# LrAc.net
KiCad netlist of a schematic drawn in Altium Designer
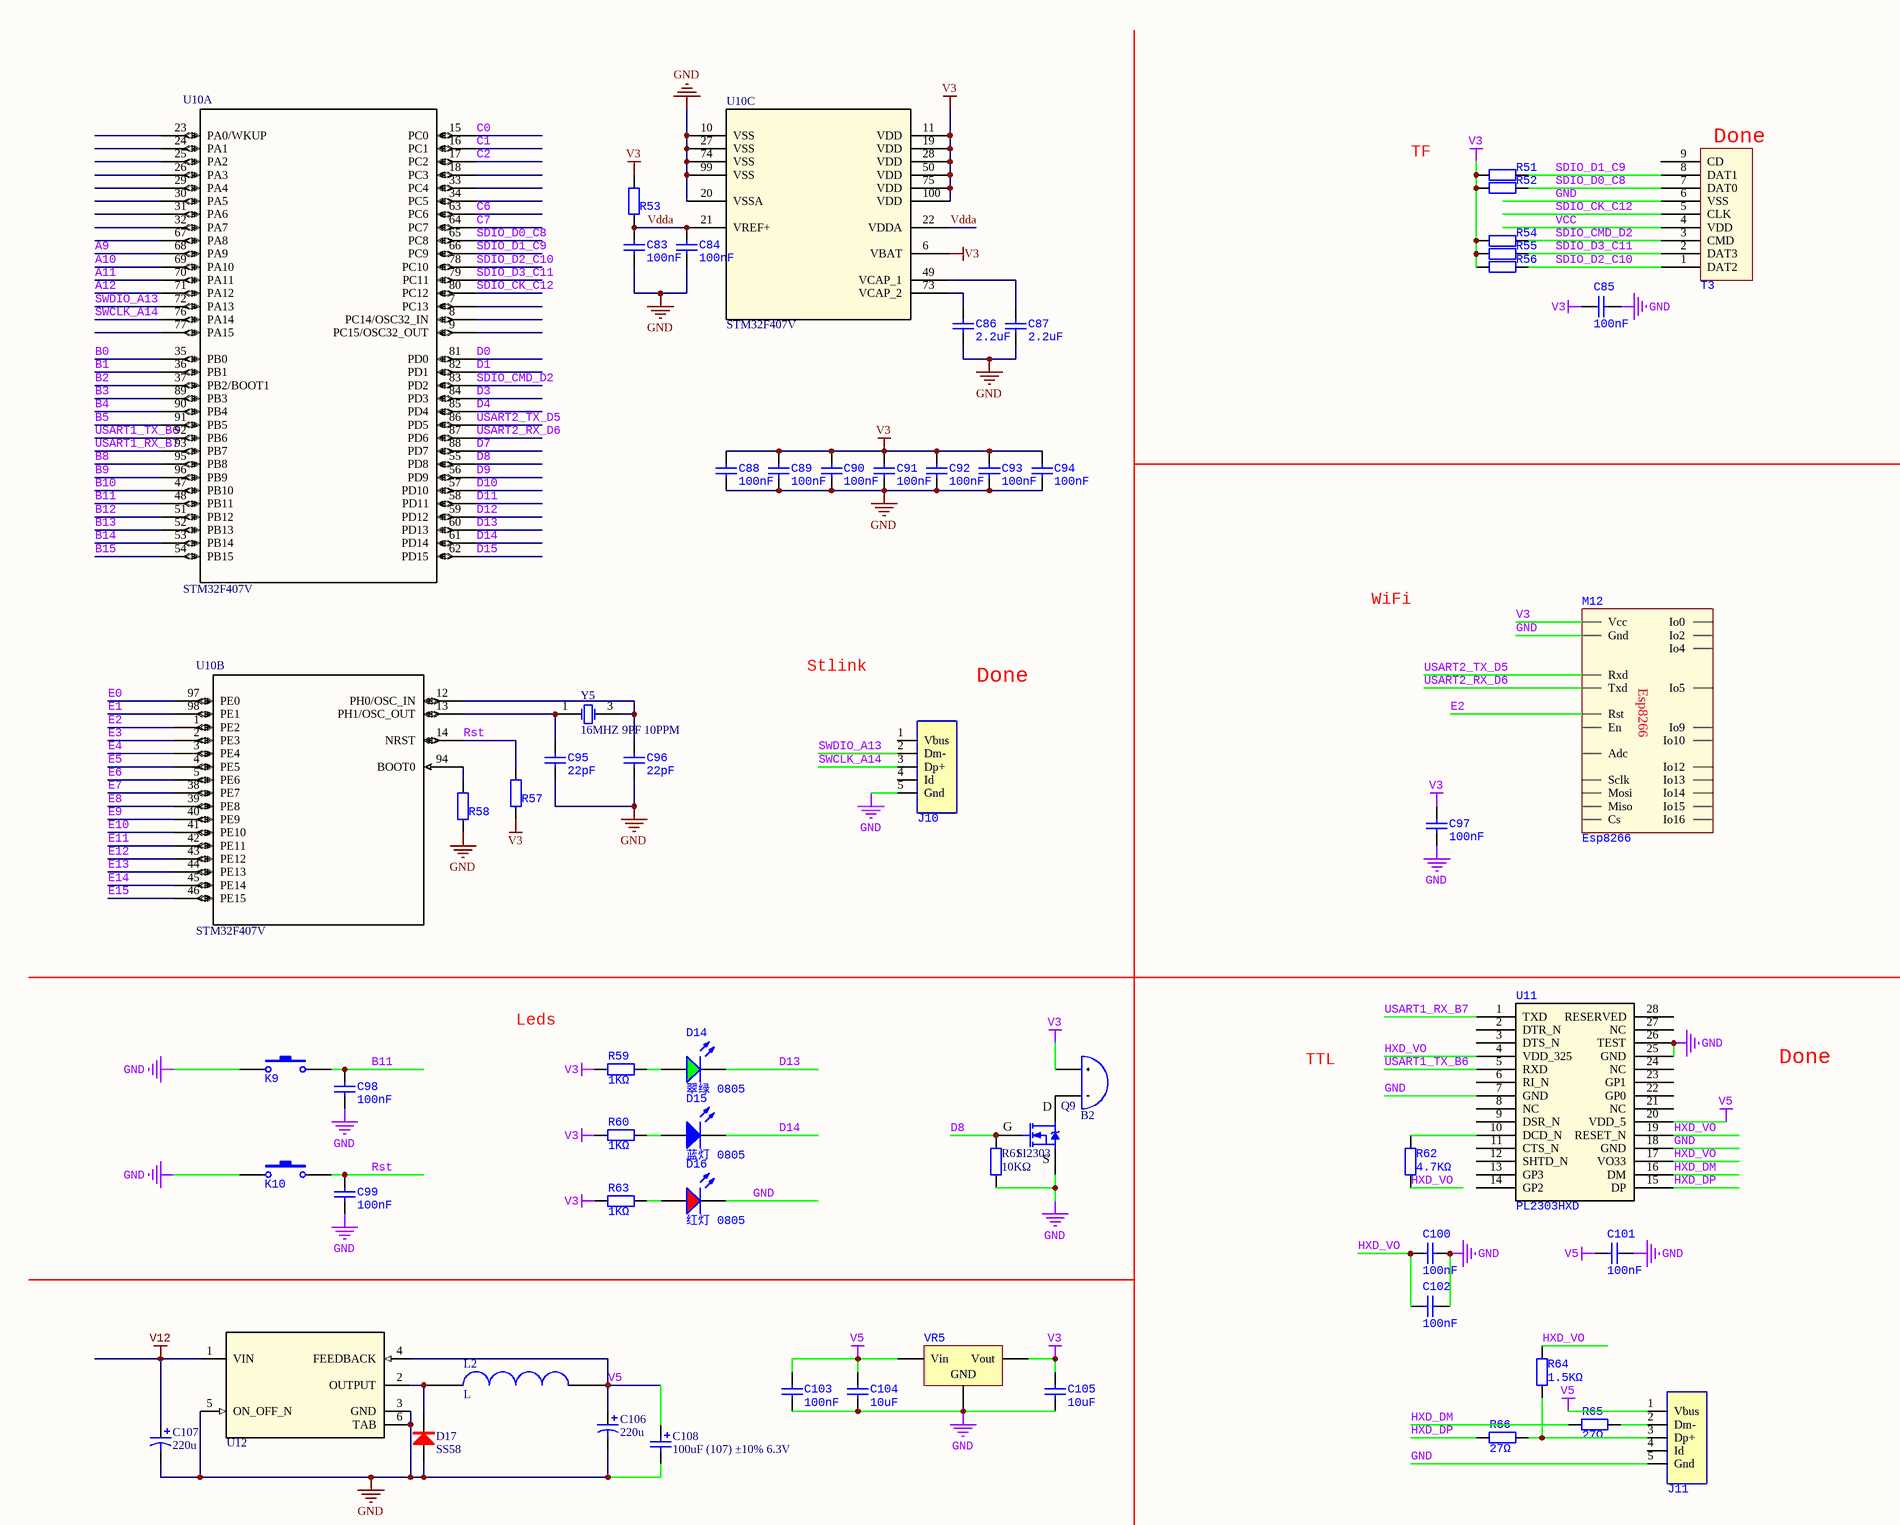
[diagram p0: LrAc.SchDoc, top]
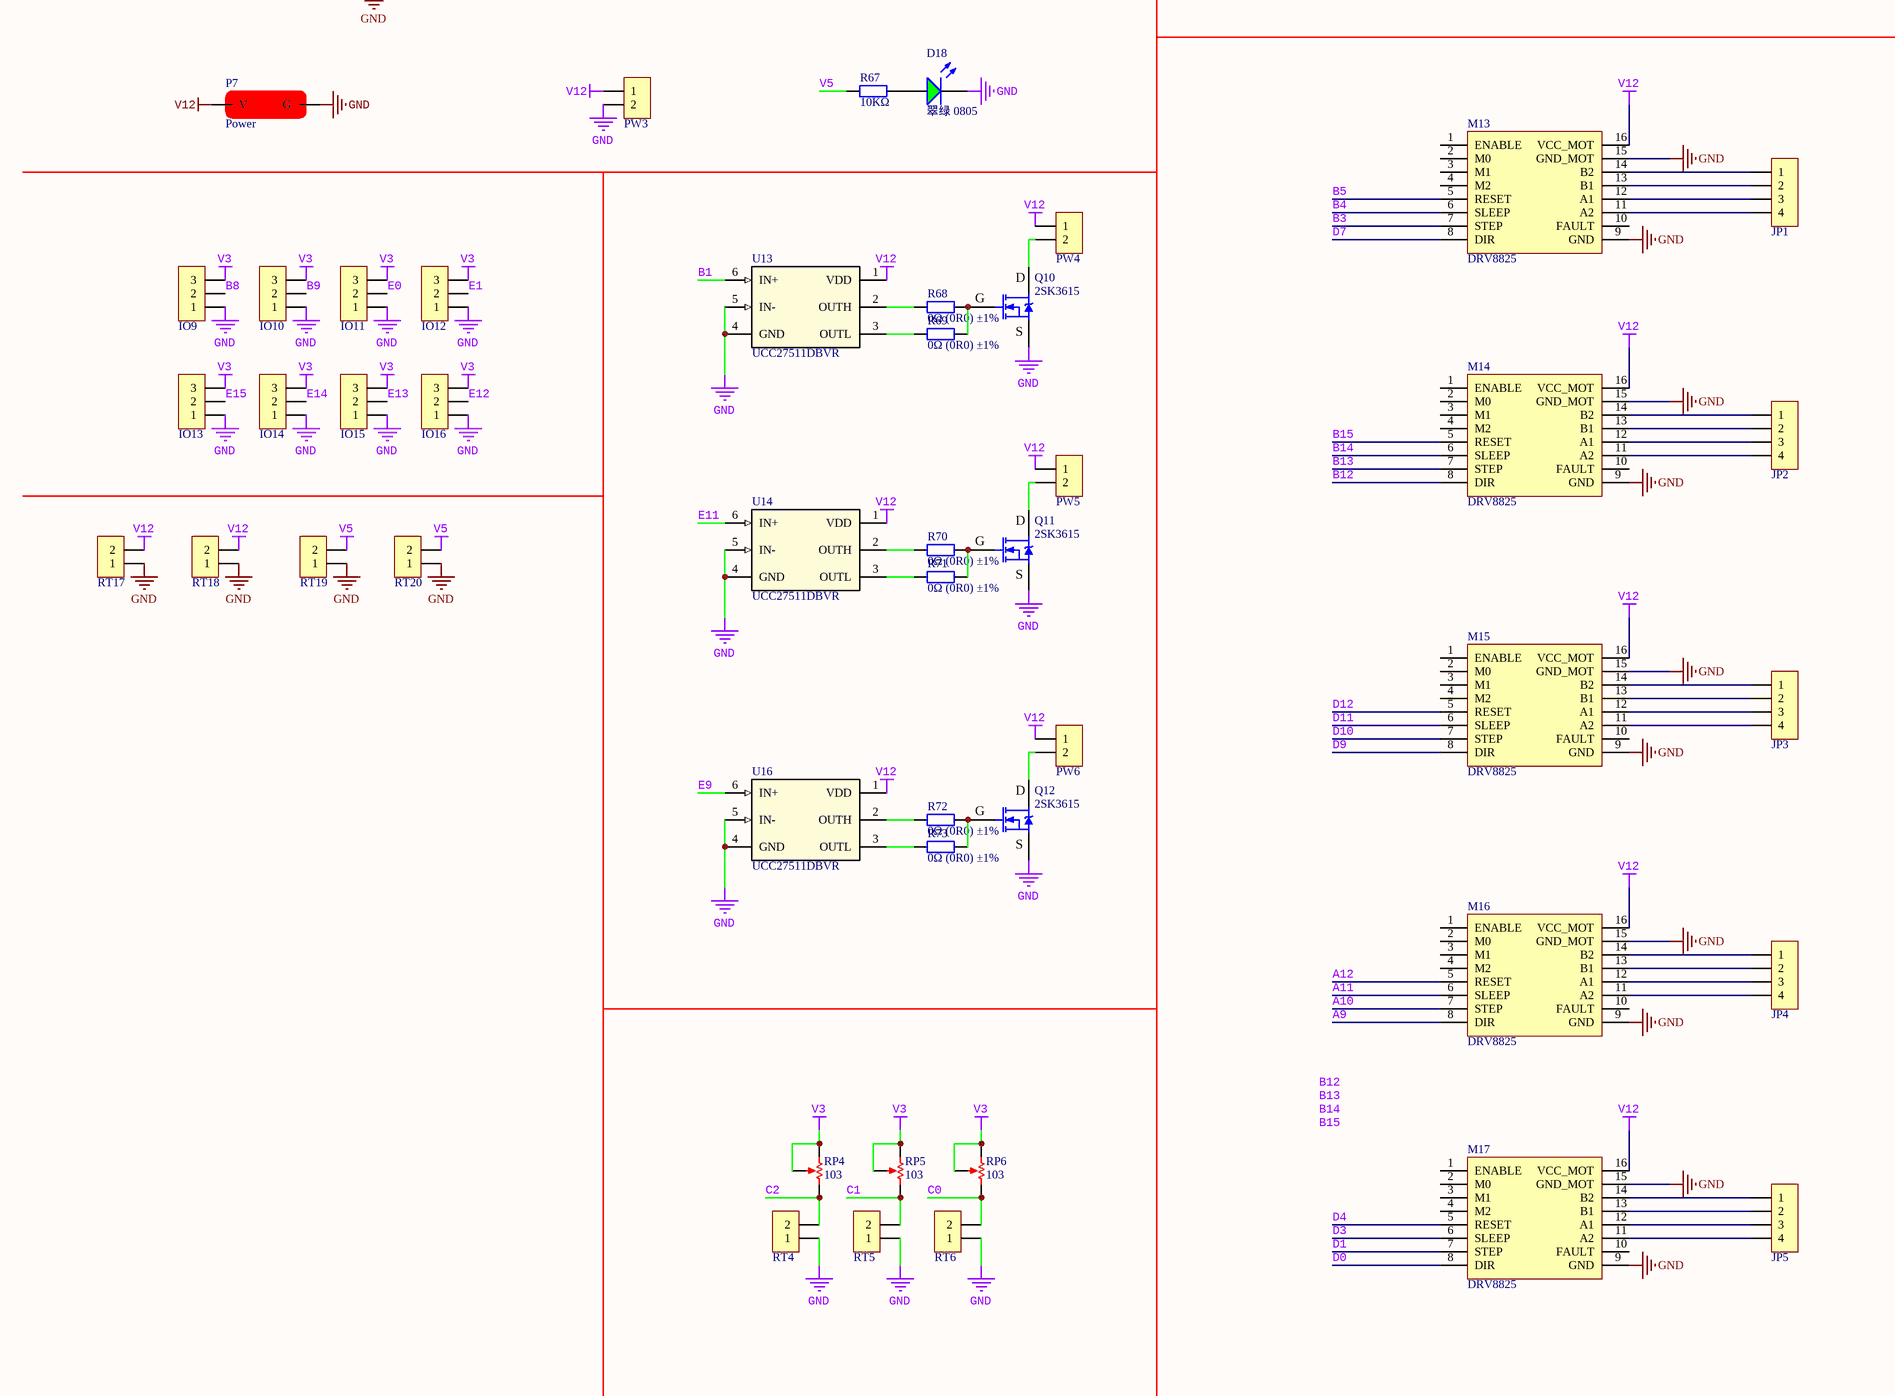
[diagram p1: LrAc.SchDoc, bottom]

(export (version "E")
  (design (tool "Eeschema 10.0.6"))
  (components
    (comp (ref "B2")
      (value "Bell")
      (footprint "BELL11.9")
      (description "蜂鸣器")
      (libsource (lib "BasicLib") (part "Bell"))
    )
    (comp (ref "C83")
      (value "100nF")
      (footprint "0603_C")
      (description "贴片电容")
      (libsource (lib "Miscellaneous Devices LC") (part "0603 100nF (104) 10% 50V"))
    )
    (comp (ref "C84")
      (value "100nF")
      (footprint "0603_C")
      (description "贴片电容")
      (libsource (lib "Miscellaneous Devices LC") (part "0603 100nF (104) 10% 50V"))
    )
    (comp (ref "C85")
      (value "100nF")
      (footprint "0603_C")
      (description "贴片电容")
      (libsource (lib "Miscellaneous Devices LC") (part "0603 100nF (104) 10% 50V"))
    )
    (comp (ref "C86")
      (value "2.2uF")
      (footprint "0603_C")
      (description "贴片电容")
      (libsource (lib "Miscellaneous Devices LC") (part "0603 100nF (104) 10% 50V"))
    )
    (comp (ref "C87")
      (value "2.2uF")
      (footprint "0603_C")
      (description "贴片电容")
      (libsource (lib "Miscellaneous Devices LC") (part "0603 100nF (104) 10% 50V"))
    )
    (comp (ref "C88")
      (value "100nF")
      (footprint "0603_C")
      (description "贴片电容")
      (libsource (lib "Miscellaneous Devices LC") (part "0603 100nF (104) 10% 50V"))
    )
    (comp (ref "C89")
      (value "100nF")
      (footprint "0603_C")
      (description "贴片电容")
      (libsource (lib "Miscellaneous Devices LC") (part "0603 100nF (104) 10% 50V"))
    )
    (comp (ref "C90")
      (value "100nF")
      (footprint "0603_C")
      (description "贴片电容")
      (libsource (lib "Miscellaneous Devices LC") (part "0603 100nF (104) 10% 50V"))
    )
    (comp (ref "C91")
      (value "100nF")
      (footprint "0603_C")
      (description "贴片电容")
      (libsource (lib "Miscellaneous Devices LC") (part "0603 100nF (104) 10% 50V"))
    )
    (comp (ref "C92")
      (value "100nF")
      (footprint "0603_C")
      (description "贴片电容")
      (libsource (lib "Miscellaneous Devices LC") (part "0603 100nF (104) 10% 50V"))
    )
    (comp (ref "C93")
      (value "100nF")
      (footprint "0603_C")
      (description "贴片电容")
      (libsource (lib "Miscellaneous Devices LC") (part "0603 100nF (104) 10% 50V"))
    )
    (comp (ref "C94")
      (value "100nF")
      (footprint "0603_C")
      (description "贴片电容")
      (libsource (lib "Miscellaneous Devices LC") (part "0603 100nF (104) 10% 50V"))
    )
    (comp (ref "C95")
      (value "22pF")
      (footprint "0603_C")
      (description "贴片电容")
      (libsource (lib "Miscellaneous Devices LC") (part "0603 100nF (104) 10% 50V"))
    )
    (comp (ref "C96")
      (value "22pF")
      (footprint "0603_C")
      (description "贴片电容")
      (libsource (lib "Miscellaneous Devices LC") (part "0603 100nF (104) 10% 50V"))
    )
    (comp (ref "C97")
      (value "100nF")
      (footprint "0603_C")
      (description "贴片电容")
      (libsource (lib "Miscellaneous Devices LC") (part "0603 100nF (104) 10% 50V"))
    )
    (comp (ref "C98")
      (value "100nF")
      (footprint "0603_C")
      (description "贴片电容")
      (libsource (lib "Miscellaneous Devices LC") (part "0603 100nF (104) 10% 50V"))
    )
    (comp (ref "C99")
      (value "100nF")
      (footprint "0603_C")
      (description "贴片电容")
      (libsource (lib "Miscellaneous Devices LC") (part "0603 100nF (104) 10% 50V"))
    )
    (comp (ref "C100")
      (value "100nF")
      (footprint "0603_C")
      (description "贴片电容")
      (libsource (lib "Miscellaneous Devices LC") (part "0603 100nF (104) 10% 50V"))
    )
    (comp (ref "C101")
      (value "100nF")
      (footprint "0603_C")
      (description "贴片电容")
      (libsource (lib "Miscellaneous Devices LC") (part "0603 100nF (104) 10% 50V"))
    )
    (comp (ref "C102")
      (value "100nF")
      (footprint "0603_C")
      (description "贴片电容")
      (libsource (lib "Miscellaneous Devices LC") (part "0603 100nF (104) 10% 50V"))
    )
    (comp (ref "C103")
      (value "100nF")
      (footprint "0603_C")
      (description "贴片电容")
      (libsource (lib "Miscellaneous Devices LC") (part "0603 100nF (104) 10% 50V"))
    )
    (comp (ref "C104")
      (value "10uF")
      (footprint "0805_C")
      (description "贴片电容")
      (libsource (lib "Miscellaneous Devices LC") (part "0805 10uF (106) 10% 25V"))
    )
    (comp (ref "C105")
      (value "10uF")
      (footprint "0805_C")
      (description "贴片电容")
      (libsource (lib "Miscellaneous Devices LC") (part "0805 10uF (106) 10% 25V"))
    )
    (comp (ref "C106")
      (value "220u")
      (footprint "CM F(10*10.2)")
      (description "Polarized Capacitor (Axial)")
      (fields (field (name "PUBLISHER") "Altium Limited"))
      (libsource (lib "BasicLib") (part "Cp"))
    )
    (comp (ref "C107")
      (value "220u")
      (footprint "CM F(10*10.2)")
      (description "Polarized Capacitor (Axial)")
      (fields (field (name "PUBLISHER") "Altium Limited"))
      (libsource (lib "BasicLib") (part "Cp"))
    )
    (comp (ref "C108")
      (value "100uF (107) ±10% 6.3V")
      (footprint "CASE-B_3528")
      (description "钽电容")
      (libsource (lib "Miscellaneous Devices LC") (part "3528 100uF (107) 10% 6.3V"))
    )
    (comp (ref "D14")
      (value "翠绿 0805")
      (footprint "0805_LED_S1")
      (description "发光二极管")
      (libsource (lib "Miscellaneous Devices LC") (part "0805 翠绿"))
    )
    (comp (ref "D15")
      (value "蓝灯 0805")
      (footprint "0805_LED_S1")
      (description "发光二极管")
      (libsource (lib "Miscellaneous Devices LC") (part "0805 蓝灯"))
    )
    (comp (ref "D16")
      (value "红灯 0805")
      (footprint "0805_LED_S1")
      (description "发光二极管")
      (libsource (lib "Miscellaneous Devices LC") (part "0805 红灯"))
    )
    (comp (ref "D17")
      (value "SS58")
      (footprint "SMA")
      (description "整流二极管")
      (fields (field (name "版权归属") "源创客"))
      (libsource (lib "BasicLib") (part "Dz"))
    )
    (comp (ref "D18")
      (value "翠绿 0805")
      (footprint "0805_LED_S1")
      (description "发光二极管")
      (libsource (lib "Miscellaneous Devices LC") (part "0805 翠绿"))
    )
    (comp (ref "IO9")
      (value "HDR-1X3")
      (footprint "XH2.54-LI-3P")
      (description "3P接插件")
      (fields (field (name "版权归属") "源创客"))
      (libsource (lib "FaceLib") (part "Header 3"))
    )
    (comp (ref "IO10")
      (value "HDR-1X3")
      (footprint "XH2.54-LI-3P")
      (description "3P接插件")
      (fields (field (name "版权归属") "源创客"))
      (libsource (lib "FaceLib") (part "Header 3"))
    )
    (comp (ref "IO11")
      (value "HDR-1X3")
      (footprint "XH2.54-LI-3P")
      (description "3P接插件")
      (fields (field (name "版权归属") "源创客"))
      (libsource (lib "FaceLib") (part "Header 3"))
    )
    (comp (ref "IO12")
      (value "HDR-1X3")
      (footprint "XH2.54-LI-3P")
      (description "3P接插件")
      (fields (field (name "版权归属") "源创客"))
      (libsource (lib "FaceLib") (part "Header 3"))
    )
    (comp (ref "IO13")
      (value "HDR-1X3")
      (footprint "XH2.54-LI-3P")
      (description "3P接插件")
      (fields (field (name "版权归属") "源创客"))
      (libsource (lib "FaceLib") (part "Header 3"))
    )
    (comp (ref "IO14")
      (value "HDR-1X3")
      (footprint "XH2.54-LI-3P")
      (description "3P接插件")
      (fields (field (name "版权归属") "源创客"))
      (libsource (lib "FaceLib") (part "Header 3"))
    )
    (comp (ref "IO15")
      (value "HDR-1X3")
      (footprint "XH2.54-LI-3P")
      (description "3P接插件")
      (fields (field (name "版权归属") "源创客"))
      (libsource (lib "FaceLib") (part "Header 3"))
    )
    (comp (ref "IO16")
      (value "HDR-1X3")
      (footprint "XH2.54-LI-3P")
      (description "3P接插件")
      (fields (field (name "版权归属") "源创客"))
      (libsource (lib "FaceLib") (part "Header 3"))
    )
    (comp (ref "J10") (value "UsbOtg") (footprint "USB-MINI-A") (libsource (lib "BasicLib") (part "UsbOtg")))
    (comp (ref "J11") (value "UsbOtg") (footprint "USB-MICRO_E") (libsource (lib "BasicLib") (part "UsbOtg")))
    (comp (ref "JP1")
      (value "HDR-1X4")
      (footprint "XH2.54-LI-4P")
      (description "4P接插件")
      (fields (field (name "版权归属") "源创客"))
      (libsource (lib "FaceLib") (part "Header 4"))
    )
    (comp (ref "JP2")
      (value "HDR-1X4")
      (footprint "XH2.54-LI-4P")
      (description "4P接插件")
      (fields (field (name "版权归属") "源创客"))
      (libsource (lib "FaceLib") (part "Header 4"))
    )
    (comp (ref "JP3")
      (value "HDR-1X4")
      (footprint "XH2.54-LI-4P")
      (description "4P接插件")
      (fields (field (name "版权归属") "源创客"))
      (libsource (lib "FaceLib") (part "Header 4"))
    )
    (comp (ref "JP4")
      (value "HDR-1X4")
      (footprint "XH2.54-LI-4P")
      (description "4P接插件")
      (fields (field (name "版权归属") "源创客"))
      (libsource (lib "FaceLib") (part "Header 4"))
    )
    (comp (ref "JP5")
      (value "HDR-1X4")
      (footprint "XH2.54-LI-4P")
      (description "4P接插件")
      (fields (field (name "版权归属") "源创客"))
      (libsource (lib "FaceLib") (part "Header 4"))
    )
    (comp (ref "K9")
      (value "SW")
      (footprint "SWITCH")
      (description "Switch")
      (libsource (lib "BasicLib") (part "SW"))
    )
    (comp (ref "K10")
      (value "SW")
      (footprint "SWITCH")
      (description "Switch")
      (libsource (lib "BasicLib") (part "SW"))
    )
    (comp (ref "L2") (value "L") (footprint "CDRH127") (libsource (lib "BasicLib") (part "L")))
    (comp (ref "M12") (value "Esp8266") (footprint "ESP8266") (libsource (lib "ModeLib") (part "Esp8266")))
    (comp (ref "M13")
      (value "DRV8825")
      (footprint "DRV8825")
      (description "步进电机驱动模块")
      (fields (field (name "版权归属") "源创客"))
      (libsource (lib "ModeLib") (part "DRV8825"))
    )
    (comp (ref "M14")
      (value "DRV8825")
      (footprint "DRV8825")
      (description "步进电机驱动模块")
      (fields (field (name "版权归属") "源创客"))
      (libsource (lib "ModeLib") (part "DRV8825"))
    )
    (comp (ref "M15")
      (value "DRV8825")
      (footprint "DRV8825")
      (description "步进电机驱动模块")
      (fields (field (name "版权归属") "源创客"))
      (libsource (lib "ModeLib") (part "DRV8825"))
    )
    (comp (ref "M16")
      (value "DRV8825")
      (footprint "DRV8825")
      (description "步进电机驱动模块")
      (fields (field (name "版权归属") "源创客"))
      (libsource (lib "ModeLib") (part "DRV8825"))
    )
    (comp (ref "M17")
      (value "DRV8825")
      (footprint "DRV8825")
      (description "步进电机驱动模块")
      (fields (field (name "版权归属") "源创客"))
      (libsource (lib "ModeLib") (part "DRV8825"))
    )
    (comp (ref "P7") (value "Power") (footprint "DC-005") (libsource (lib "BasicLib") (part "Power")))
    (comp (ref "PW3")
      (value "HDR-1X2")
      (footprint "2PIN-5.08A")
      (description "2P接插件")
      (fields (field (name "版权归属") "源创客"))
      (libsource (lib "FaceLib") (part "Header 2"))
    )
    (comp (ref "PW4")
      (value "HDR-1X2")
      (footprint "2PIN-5.08A")
      (description "2P接插件")
      (fields (field (name "版权归属") "源创客"))
      (libsource (lib "FaceLib") (part "Header 2"))
    )
    (comp (ref "PW5")
      (value "HDR-1X2")
      (footprint "2PIN-5.08A")
      (description "2P接插件")
      (fields (field (name "版权归属") "源创客"))
      (libsource (lib "FaceLib") (part "Header 2"))
    )
    (comp (ref "PW6")
      (value "HDR-1X2")
      (footprint "2PIN-5.08A")
      (description "2P接插件")
      (fields (field (name "版权归属") "源创客"))
      (libsource (lib "FaceLib") (part "Header 2"))
    )
    (comp (ref "Q9")
      (value "SI2303")
      (footprint "SI2302")
      (description "N沟场效应管")
      (fields (field (name "版权归属") "源创客"))
      (libsource (lib "BasicLib") (part "NMOS"))
    )
    (comp (ref "Q10")
      (value "2SK3615")
      (footprint "IRF3205")
      (description "N沟场效应管")
      (fields (field (name "版权归属") "源创客"))
      (libsource (lib "BasicLib") (part "NMOS"))
    )
    (comp (ref "Q11")
      (value "2SK3615")
      (footprint "IRF3205")
      (description "N沟场效应管")
      (fields (field (name "版权归属") "源创客"))
      (libsource (lib "BasicLib") (part "NMOS"))
    )
    (comp (ref "Q12")
      (value "2SK3615")
      (footprint "IRF3205")
      (description "N沟场效应管")
      (fields (field (name "版权归属") "源创客"))
      (libsource (lib "BasicLib") (part "NMOS"))
    )
    (comp (ref "R51")
      (value "47KΩ")
      (footprint "0603_R")
      (description "贴片电阻")
      (libsource (lib "") (part "0603 47KΩ (4702) 1%_1"))
    )
    (comp (ref "R52")
      (value "47KΩ")
      (footprint "0603_R")
      (description "贴片电阻")
      (libsource (lib "") (part "0603 47KΩ (4702) 1%_1"))
    )
    (comp (ref "R53")
      (value "10Ω")
      (footprint "0603_R")
      (description "贴片电阻")
      (libsource (lib "Miscellaneous Devices LC") (part "0603 47KΩ (4702) 1%"))
    )
    (comp (ref "R54")
      (value "47KΩ")
      (footprint "0603_R")
      (description "贴片电阻")
      (libsource (lib "") (part "0603 47KΩ (4702) 1%_1"))
    )
    (comp (ref "R55")
      (value "47KΩ")
      (footprint "0603_R")
      (description "贴片电阻")
      (libsource (lib "") (part "0603 47KΩ (4702) 1%_1"))
    )
    (comp (ref "R56")
      (value "47KΩ")
      (footprint "0603_R")
      (description "贴片电阻")
      (libsource (lib "") (part "0603 47KΩ (4702) 1%_1"))
    )
    (comp (ref "R57")
      (value "47KΩ")
      (footprint "0603_R")
      (description "贴片电阻")
      (libsource (lib "Miscellaneous Devices LC") (part "0603 47KΩ (4702) 1%"))
    )
    (comp (ref "R58")
      (value "47KΩ")
      (footprint "0603_R")
      (description "贴片电阻")
      (libsource (lib "Miscellaneous Devices LC") (part "0603 47KΩ (4702) 1%"))
    )
    (comp (ref "R59")
      (value "1KΩ")
      (footprint "0603_R")
      (description "贴片电阻")
      (libsource (lib "Miscellaneous Devices LC") (part "0603 10KΩ (1002) 1%"))
    )
    (comp (ref "R60")
      (value "1KΩ")
      (footprint "0603_R")
      (description "贴片电阻")
      (libsource (lib "Miscellaneous Devices LC") (part "0603 10KΩ (1002) 1%"))
    )
    (comp (ref "R61")
      (value "10KΩ")
      (footprint "0805_R")
      (description "贴片电阻")
      (libsource (lib "") (part "0805 10KΩ (1002) 1%_1"))
    )
    (comp (ref "R62")
      (value "4.7KΩ")
      (footprint "0603_R")
      (description "贴片电阻")
      (libsource (lib "") (part "0603 10KΩ (1002) 1%_3"))
    )
    (comp (ref "R63")
      (value "1KΩ")
      (footprint "0603_R")
      (description "贴片电阻")
      (libsource (lib "Miscellaneous Devices LC") (part "0603 10KΩ (1002) 1%"))
    )
    (comp (ref "R64")
      (value "1.5KΩ")
      (footprint "0603_R")
      (description "贴片电阻")
      (libsource (lib "") (part "0603 10KΩ (1002) 1%_2"))
    )
    (comp (ref "R65")
      (value "27Ω")
      (footprint "0603_R")
      (description "贴片电阻")
      (libsource (lib "") (part "0603 10KΩ (1002) 1%_1"))
    )
    (comp (ref "R66")
      (value "27Ω")
      (footprint "0603_R")
      (description "贴片电阻")
      (libsource (lib "") (part "0603 10KΩ (1002) 1%_1"))
    )
    (comp (ref "R67")
      (value "10KΩ")
      (footprint "0805_R")
      (description "贴片电阻")
      (libsource (lib "Miscellaneous Devices LC") (part "0805 10KΩ (1002) 1%"))
    )
    (comp (ref "R68")
      (value "0Ω (0R0) ±1%")
      (footprint "0805_R")
      (description "贴片电阻")
      (libsource (lib "Miscellaneous Devices LC") (part "0805 0Ω (0R0) 1%"))
    )
    (comp (ref "R69")
      (value "0Ω (0R0) ±1%")
      (footprint "0805_R")
      (description "贴片电阻")
      (libsource (lib "Miscellaneous Devices LC") (part "0805 0Ω (0R0) 1%"))
    )
    (comp (ref "R70")
      (value "0Ω (0R0) ±1%")
      (footprint "0805_R")
      (description "贴片电阻")
      (libsource (lib "Miscellaneous Devices LC") (part "0805 0Ω (0R0) 1%"))
    )
    (comp (ref "R71")
      (value "0Ω (0R0) ±1%")
      (footprint "0805_R")
      (description "贴片电阻")
      (libsource (lib "Miscellaneous Devices LC") (part "0805 0Ω (0R0) 1%"))
    )
    (comp (ref "R72")
      (value "0Ω (0R0) ±1%")
      (footprint "0805_R")
      (description "贴片电阻")
      (libsource (lib "Miscellaneous Devices LC") (part "0805 0Ω (0R0) 1%"))
    )
    (comp (ref "R73")
      (value "0Ω (0R0) ±1%")
      (footprint "0805_R")
      (description "贴片电阻")
      (libsource (lib "Miscellaneous Devices LC") (part "0805 0Ω (0R0) 1%"))
    )
    (comp (ref "RP4")
      (value "103")
      (footprint "RP3362P")
      (description "Potentiometer")
      (fields (field (name "PUBLISHER") "Altium Limited"))
      (libsource (lib "BasicLib") (part "Rp"))
    )
    (comp (ref "RP5")
      (value "103")
      (footprint "RP3362P")
      (description "Potentiometer")
      (fields (field (name "PUBLISHER") "Altium Limited"))
      (libsource (lib "BasicLib") (part "Rp"))
    )
    (comp (ref "RP6")
      (value "103")
      (footprint "RP3362P")
      (description "Potentiometer")
      (fields (field (name "PUBLISHER") "Altium Limited"))
      (libsource (lib "BasicLib") (part "Rp"))
    )
    (comp (ref "RT4")
      (value "HDR-1X2")
      (footprint "XH2.54-LI-2P")
      (description "2P接插件")
      (fields (field (name "版权归属") "源创客"))
      (libsource (lib "") (part "Header 2_1"))
    )
    (comp (ref "RT5")
      (value "HDR-1X2")
      (footprint "XH2.54-LI-2P")
      (description "2P接插件")
      (fields (field (name "版权归属") "源创客"))
      (libsource (lib "") (part "Header 2_1"))
    )
    (comp (ref "RT6")
      (value "HDR-1X2")
      (footprint "XH2.54-LI-2P")
      (description "2P接插件")
      (fields (field (name "版权归属") "源创客"))
      (libsource (lib "") (part "Header 2_1"))
    )
    (comp (ref "RT17")
      (value "HDR-1X2")
      (footprint "XH2.54-LI-2P")
      (description "2P接插件")
      (fields (field (name "版权归属") "源创客"))
      (libsource (lib "") (part "Header 2_1"))
    )
    (comp (ref "RT18")
      (value "HDR-1X2")
      (footprint "XH2.54-LI-2P")
      (description "2P接插件")
      (fields (field (name "版权归属") "源创客"))
      (libsource (lib "") (part "Header 2_1"))
    )
    (comp (ref "RT19")
      (value "HDR-1X2")
      (footprint "XH2.54-LI-2P")
      (description "2P接插件")
      (fields (field (name "版权归属") "源创客"))
      (libsource (lib "") (part "Header 2_1"))
    )
    (comp (ref "RT20")
      (value "HDR-1X2")
      (footprint "XH2.54-LI-2P")
      (description "2P接插件")
      (fields (field (name "版权归属") "源创客"))
      (libsource (lib "") (part "Header 2_1"))
    )
    (comp (ref "T3") (value "TFCard") (footprint "TF-CARD") (libsource (lib "BasicLib") (part "TFCard")))
    (comp (ref "U10")
      (value "STM32F407V")
      (footprint "LQFP100")
      (description "Imported")
      (fields
        (field (name "MANUFACTURER_PART_NUMBER") "stm32f4xxv2")
        (field (name "COPYRIGHT") "Copyright (C) 2016 Accelerated Designs. All rights reserved")
      )
      (libsource (lib "Lib") (part "STM32F407V"))
    )
    (comp (ref "U11")
      (value "PL2303HXD")
      (footprint "SSOP28")
      (description "Driver")
      (fields
        (field (name "MANUFACTURER_PART_NUMBER") "tlc5916-q1_d_16")
        (field (name "GENERIC_PART_NUMBER") "TLC5916-Q1")
      )
      (libsource (lib "ChipLib") (part "PL2303HXD"))
    )
    (comp (ref "U12")
      (value "LM2596")
      (footprint "TO263")
      (description "Imported")
      (fields
        (field (name "PARTNUMBER") "LM2596SX-ADJ/NOPB")
        (field (name "ALTERNATE_PARTNUMBER") "LM2596S-ADJ/NOPB")
      )
      (libsource (lib "ChipLib") (part "LM2596"))
    )
    (comp (ref "U13")
      (value "UCC27511DBVR")
      (footprint "DBV0006A_N")
      (description "Imported")
      (fields
        (field (name "ALTERNATE_PARTNUMBER") "UCC27511DBVT")
        (field (name "MANUFACTURER") "Texas Instruments")
      )
      (libsource (lib "ChipLib") (part "UCC27511DBVR"))
    )
    (comp (ref "U14")
      (value "UCC27511DBVR")
      (footprint "DBV0006A_N")
      (description "Imported")
      (fields
        (field (name "ALTERNATE_PARTNUMBER") "UCC27511DBVT")
        (field (name "MANUFACTURER") "Texas Instruments")
      )
      (libsource (lib "ChipLib") (part "UCC27511DBVR"))
    )
    (comp (ref "U16")
      (value "UCC27511DBVR")
      (footprint "DBV0006A_N")
      (description "Imported")
      (fields
        (field (name "ALTERNATE_PARTNUMBER") "UCC27511DBVT")
        (field (name "MANUFACTURER") "Texas Instruments")
      )
      (libsource (lib "ChipLib") (part "UCC27511DBVR"))
    )
    (comp (ref "VR5")
      (value "AMS1117-3.3")
      (footprint "SOT-223")
      (description "低压差线性稳压(LDO)")
      (libsource (lib "Miscellaneous Devices LC") (part "SOT-223 AMS1117-3.3"))
    )
    (comp (ref "Y5")
      (value "16MHZ 9PF 10PPM")
      (footprint "SMD-3225_4P")
      (description "贴片晶振")
      (libsource (lib "Miscellaneous Devices LC") (part "SMD-3225_4P  16MHZ 9PF 10PPM"))
    )
  )
  (nets
    (net (code "1") (name "/A9") (class "Default")
      (node (ref "M16") (pin "8") (pinfunction "DIR_8") (pintype "passive"))
      (node (ref "U10") (pin "68") (pinfunction "PA9_68") (pintype "bidirectional"))
    )
    (net (code "2") (name "/A10") (class "Default")
      (node (ref "M16") (pin "7") (pinfunction "STEP_7") (pintype "passive"))
      (node (ref "U10") (pin "69") (pinfunction "PA10_69") (pintype "bidirectional"))
    )
    (net (code "3") (name "/A11") (class "Default")
      (node (ref "M16") (pin "6") (pinfunction "SLEEP_6") (pintype "passive"))
      (node (ref "U10") (pin "70") (pinfunction "PA11_70") (pintype "bidirectional"))
    )
    (net (code "4") (name "/A12") (class "Default")
      (node (ref "M16") (pin "5") (pinfunction "RESET_5") (pintype "passive"))
      (node (ref "U10") (pin "71") (pinfunction "PA12_71") (pintype "bidirectional"))
    )
    (net (code "5") (name "/B0") (class "Default")
      (node (ref "U10") (pin "35") (pinfunction "PB0_35") (pintype "bidirectional"))
    )
    (net (code "6") (name "/B1") (class "Default")
      (node (ref "U10") (pin "36") (pinfunction "PB1_36") (pintype "bidirectional"))
      (node (ref "U13") (pin "6") (pinfunction "IN+_6") (pintype "input"))
    )
    (net (code "7") (name "/B2") (class "Default")
      (node (ref "U10") (pin "37") (pinfunction "PB2/BOOT1_37") (pintype "bidirectional"))
    )
    (net (code "8") (name "/B3") (class "Default")
      (node (ref "M13") (pin "7") (pinfunction "STEP_7") (pintype "passive"))
      (node (ref "U10") (pin "89") (pinfunction "PB3_89") (pintype "bidirectional"))
    )
    (net (code "9") (name "/B4") (class "Default")
      (node (ref "M13") (pin "6") (pinfunction "SLEEP_6") (pintype "passive"))
      (node (ref "U10") (pin "90") (pinfunction "PB4_90") (pintype "bidirectional"))
    )
    (net (code "10") (name "/B5") (class "Default")
      (node (ref "M13") (pin "5") (pinfunction "RESET_5") (pintype "passive"))
      (node (ref "U10") (pin "91") (pinfunction "PB5_91") (pintype "bidirectional"))
    )
    (net (code "11") (name "/B8") (class "Default")
      (node (ref "IO9") (pin "2") (pinfunction "2_2") (pintype "passive"))
      (node (ref "U10") (pin "95") (pinfunction "PB8_95") (pintype "bidirectional"))
    )
    (net (code "12") (name "/B9") (class "Default")
      (node (ref "IO10") (pin "2") (pinfunction "2_2") (pintype "passive"))
      (node (ref "U10") (pin "96") (pinfunction "PB9_96") (pintype "bidirectional"))
    )
    (net (code "13") (name "/B10") (class "Default")
      (node (ref "U10") (pin "47") (pinfunction "PB10_47") (pintype "bidirectional"))
    )
    (net (code "14") (name "/B11") (class "Default")
      (node (ref "C98") (pin "2") (pinfunction "2_2") (pintype "passive"))
      (node (ref "K9") (pin "2") (pinfunction "2_2") (pintype "passive"))
      (node (ref "U10") (pin "48") (pinfunction "PB11_48") (pintype "bidirectional"))
    )
    (net (code "15") (name "/B12") (class "Default")
      (node (ref "M14") (pin "8") (pinfunction "DIR_8") (pintype "passive"))
      (node (ref "U10") (pin "51") (pinfunction "PB12_51") (pintype "bidirectional"))
    )
    (net (code "16") (name "/B13") (class "Default")
      (node (ref "M14") (pin "7") (pinfunction "STEP_7") (pintype "passive"))
      (node (ref "U10") (pin "52") (pinfunction "PB13_52") (pintype "bidirectional"))
    )
    (net (code "17") (name "/B14") (class "Default")
      (node (ref "M14") (pin "6") (pinfunction "SLEEP_6") (pintype "passive"))
      (node (ref "U10") (pin "53") (pinfunction "PB14_53") (pintype "bidirectional"))
    )
    (net (code "18") (name "/B15") (class "Default")
      (node (ref "M14") (pin "5") (pinfunction "RESET_5") (pintype "passive"))
      (node (ref "U10") (pin "54") (pinfunction "PB15_54") (pintype "bidirectional"))
    )
    (net (code "19") (name "/C0") (class "Default")
      (node (ref "RP6") (pin "1") (pinfunction "BOT_1") (pintype "passive"))
      (node (ref "RT6") (pin "2") (pinfunction "2_2") (pintype "passive"))
      (node (ref "U10") (pin "15") (pinfunction "PC0_15") (pintype "bidirectional"))
    )
    (net (code "20") (name "/C1") (class "Default")
      (node (ref "RP5") (pin "1") (pinfunction "BOT_1") (pintype "passive"))
      (node (ref "RT5") (pin "2") (pinfunction "2_2") (pintype "passive"))
      (node (ref "U10") (pin "16") (pinfunction "PC1_16") (pintype "bidirectional"))
    )
    (net (code "21") (name "/C2") (class "Default")
      (node (ref "RP4") (pin "1") (pinfunction "BOT_1") (pintype "passive"))
      (node (ref "RT4") (pin "2") (pinfunction "2_2") (pintype "passive"))
      (node (ref "U10") (pin "17") (pinfunction "PC2_17") (pintype "bidirectional"))
    )
    (net (code "22") (name "/C6") (class "Default")
      (node (ref "U10") (pin "63") (pinfunction "PC6_63") (pintype "bidirectional"))
    )
    (net (code "23") (name "/C7") (class "Default")
      (node (ref "U10") (pin "64") (pinfunction "PC7_64") (pintype "bidirectional"))
    )
    (net (code "24") (name "/D0") (class "Default")
      (node (ref "M17") (pin "8") (pinfunction "DIR_8") (pintype "passive"))
      (node (ref "U10") (pin "81") (pinfunction "PD0_81") (pintype "bidirectional"))
    )
    (net (code "25") (name "/D1") (class "Default")
      (node (ref "M17") (pin "7") (pinfunction "STEP_7") (pintype "passive"))
      (node (ref "U10") (pin "82") (pinfunction "PD1_82") (pintype "bidirectional"))
    )
    (net (code "26") (name "/D3") (class "Default")
      (node (ref "M17") (pin "6") (pinfunction "SLEEP_6") (pintype "passive"))
      (node (ref "U10") (pin "84") (pinfunction "PD3_84") (pintype "bidirectional"))
    )
    (net (code "27") (name "/D4") (class "Default")
      (node (ref "M17") (pin "5") (pinfunction "RESET_5") (pintype "passive"))
      (node (ref "U10") (pin "85") (pinfunction "PD4_85") (pintype "bidirectional"))
    )
    (net (code "28") (name "/D7") (class "Default")
      (node (ref "M13") (pin "8") (pinfunction "DIR_8") (pintype "passive"))
      (node (ref "U10") (pin "88") (pinfunction "PD7_88") (pintype "bidirectional"))
    )
    (net (code "29") (name "/D8") (class "Default")
      (node (ref "Q9") (pin "1") (pinfunction "G_1") (pintype "passive"))
      (node (ref "R61") (pin "2") (pinfunction "2_2") (pintype "passive"))
      (node (ref "U10") (pin "55") (pinfunction "PD8_55") (pintype "bidirectional"))
    )
    (net (code "30") (name "/D9") (class "Default")
      (node (ref "M15") (pin "8") (pinfunction "DIR_8") (pintype "passive"))
      (node (ref "U10") (pin "56") (pinfunction "PD9_56") (pintype "bidirectional"))
    )
    (net (code "31") (name "/D10") (class "Default")
      (node (ref "M15") (pin "7") (pinfunction "STEP_7") (pintype "passive"))
      (node (ref "U10") (pin "57") (pinfunction "PD10_57") (pintype "bidirectional"))
    )
    (net (code "32") (name "/D11") (class "Default")
      (node (ref "M15") (pin "6") (pinfunction "SLEEP_6") (pintype "passive"))
      (node (ref "U10") (pin "58") (pinfunction "PD11_58") (pintype "bidirectional"))
    )
    (net (code "33") (name "/D12") (class "Default")
      (node (ref "M15") (pin "5") (pinfunction "RESET_5") (pintype "passive"))
      (node (ref "U10") (pin "59") (pinfunction "PD12_59") (pintype "bidirectional"))
    )
    (net (code "34") (name "/D13") (class "Default")
      (node (ref "D14") (pin "K") (pinfunction "K_K") (pintype "passive"))
      (node (ref "U10") (pin "60") (pinfunction "PD13_60") (pintype "bidirectional"))
    )
    (net (code "35") (name "/D14") (class "Default")
      (node (ref "D15") (pin "K") (pinfunction "K_K") (pintype "passive"))
      (node (ref "U10") (pin "61") (pinfunction "PD14_61") (pintype "bidirectional"))
    )
    (net (code "36") (name "/D15") (class "Default")
      (node (ref "U10") (pin "62") (pinfunction "PD15_62") (pintype "bidirectional"))
    )
    (net (code "37") (name "/E0") (class "Default")
      (node (ref "IO11") (pin "2") (pinfunction "2_2") (pintype "passive"))
      (node (ref "U10") (pin "97") (pinfunction "PE0_97") (pintype "bidirectional"))
    )
    (net (code "38") (name "/E1") (class "Default")
      (node (ref "IO12") (pin "2") (pinfunction "2_2") (pintype "passive"))
      (node (ref "U10") (pin "98") (pinfunction "PE1_98") (pintype "bidirectional"))
    )
    (net (code "39") (name "/E2") (class "Default")
      (node (ref "M12") (pin "1") (pinfunction "Rst_1") (pintype "passive"))
      (node (ref "U10") (pin "1") (pinfunction "PE2_1") (pintype "bidirectional"))
    )
    (net (code "40") (name "/E3") (class "Default")
      (node (ref "U10") (pin "2") (pinfunction "PE3_2") (pintype "bidirectional"))
    )
    (net (code "41") (name "/E4") (class "Default")
      (node (ref "U10") (pin "3") (pinfunction "PE4_3") (pintype "bidirectional"))
    )
    (net (code "42") (name "/E5") (class "Default")
      (node (ref "U10") (pin "4") (pinfunction "PE5_4") (pintype "bidirectional"))
    )
    (net (code "43") (name "/E6") (class "Default")
      (node (ref "U10") (pin "5") (pinfunction "PE6_5") (pintype "bidirectional"))
    )
    (net (code "44") (name "/E7") (class "Default")
      (node (ref "U10") (pin "38") (pinfunction "PE7_38") (pintype "bidirectional"))
    )
    (net (code "45") (name "/E8") (class "Default")
      (node (ref "U10") (pin "39") (pinfunction "PE8_39") (pintype "bidirectional"))
    )
    (net (code "46") (name "/E9") (class "Default")
      (node (ref "U10") (pin "40") (pinfunction "PE9_40") (pintype "bidirectional"))
      (node (ref "U16") (pin "6") (pinfunction "IN+_6") (pintype "input"))
    )
    (net (code "47") (name "/E10") (class "Default")
      (node (ref "U10") (pin "41") (pinfunction "PE10_41") (pintype "bidirectional"))
    )
    (net (code "48") (name "/E11") (class "Default")
      (node (ref "U10") (pin "42") (pinfunction "PE11_42") (pintype "bidirectional"))
      (node (ref "U14") (pin "6") (pinfunction "IN+_6") (pintype "input"))
    )
    (net (code "49") (name "/E12") (class "Default")
      (node (ref "IO16") (pin "2") (pinfunction "2_2") (pintype "passive"))
      (node (ref "U10") (pin "43") (pinfunction "PE12_43") (pintype "bidirectional"))
    )
    (net (code "50") (name "/E13") (class "Default")
      (node (ref "IO15") (pin "2") (pinfunction "2_2") (pintype "passive"))
      (node (ref "U10") (pin "44") (pinfunction "PE13_44") (pintype "bidirectional"))
    )
    (net (code "51") (name "/E14") (class "Default")
      (node (ref "IO14") (pin "2") (pinfunction "2_2") (pintype "passive"))
      (node (ref "U10") (pin "45") (pinfunction "PE14_45") (pintype "bidirectional"))
    )
    (net (code "52") (name "/E15") (class "Default")
      (node (ref "IO13") (pin "2") (pinfunction "2_2") (pintype "passive"))
      (node (ref "U10") (pin "46") (pinfunction "PE15_46") (pintype "bidirectional"))
    )
    (net (code "53") (name "/HXD_DM") (class "Default")
      (node (ref "R65") (pin "1") (pinfunction "1_1") (pintype "passive"))
      (node (ref "U11") (pin "16") (pinfunction "DM_16") (pintype "power_in"))
    )
    (net (code "54") (name "/HXD_DP") (class "Default")
      (node (ref "R66") (pin "1") (pinfunction "1_1") (pintype "passive"))
      (node (ref "U11") (pin "15") (pinfunction "DP_15") (pintype "power_in"))
    )
    (net (code "55") (name "/HXD_VO") (class "Default")
      (node (ref "C100") (pin "2") (pinfunction "2_2") (pintype "passive"))
      (node (ref "C102") (pin "2") (pinfunction "2_2") (pintype "passive"))
      (node (ref "R62") (pin "2") (pinfunction "2_2") (pintype "passive"))
      (node (ref "R64") (pin "2") (pinfunction "2_2") (pintype "passive"))
      (node (ref "U11") (pin "17") (pinfunction "VO33_17") (pintype "power_in"))
      (node (ref "U11") (pin "19") (pinfunction "RESET_N_19") (pintype "power_in"))
      (node (ref "U11") (pin "4") (pinfunction "VDD_325_4") (pintype "power_in"))
    )
    (net (code "56") (name "/Rst") (class "Default")
      (node (ref "C99") (pin "2") (pinfunction "2_2") (pintype "passive"))
      (node (ref "K10") (pin "2") (pinfunction "2_2") (pintype "passive"))
      (node (ref "R57") (pin "2") (pinfunction "2_2") (pintype "passive"))
      (node (ref "U10") (pin "14") (pinfunction "NRST_14") (pintype "bidirectional"))
    )
    (net (code "57") (name "/SDIO_CK_C12") (class "Default")
      (node (ref "T3") (pin "5") (pinfunction "CLK_5") (pintype "passive"))
      (node (ref "U10") (pin "80") (pinfunction "PC12_80") (pintype "bidirectional"))
    )
    (net (code "58") (name "/SDIO_CMD_D2") (class "Default")
      (node (ref "R54") (pin "2") (pinfunction "2_2") (pintype "passive"))
      (node (ref "T3") (pin "3") (pinfunction "CMD_3") (pintype "passive"))
      (node (ref "U10") (pin "83") (pinfunction "PD2_83") (pintype "bidirectional"))
    )
    (net (code "59") (name "/SDIO_D0_C8") (class "Default")
      (node (ref "R52") (pin "2") (pinfunction "2_2") (pintype "passive"))
      (node (ref "T3") (pin "7") (pinfunction "DAT0_7") (pintype "passive"))
      (node (ref "U10") (pin "65") (pinfunction "PC8_65") (pintype "bidirectional"))
    )
    (net (code "60") (name "/SDIO_D1_C9") (class "Default")
      (node (ref "R51") (pin "2") (pinfunction "2_2") (pintype "passive"))
      (node (ref "T3") (pin "8") (pinfunction "DAT1_8") (pintype "passive"))
      (node (ref "U10") (pin "66") (pinfunction "PC9_66") (pintype "bidirectional"))
    )
    (net (code "61") (name "/SDIO_D2_C10") (class "Default")
      (node (ref "R56") (pin "2") (pinfunction "2_2") (pintype "passive"))
      (node (ref "T3") (pin "1") (pinfunction "DAT2_1") (pintype "passive"))
      (node (ref "U10") (pin "78") (pinfunction "PC10_78") (pintype "bidirectional"))
    )
    (net (code "62") (name "/SDIO_D3_C11") (class "Default")
      (node (ref "R55") (pin "2") (pinfunction "2_2") (pintype "passive"))
      (node (ref "T3") (pin "2") (pinfunction "DAT3_2") (pintype "passive"))
      (node (ref "U10") (pin "79") (pinfunction "PC11_79") (pintype "bidirectional"))
    )
    (net (code "63") (name "/SWCLK_A14") (class "Default")
      (node (ref "J10") (pin "3") (pinfunction "Dp+_3") (pintype "passive"))
      (node (ref "U10") (pin "76") (pinfunction "PA14_76") (pintype "bidirectional"))
    )
    (net (code "64") (name "/SWDIO_A13") (class "Default")
      (node (ref "J10") (pin "2") (pinfunction "Dm-_2") (pintype "passive"))
      (node (ref "U10") (pin "72") (pinfunction "PA13_72") (pintype "bidirectional"))
    )
    (net (code "65") (name "/USART1_RX_B7") (class "Default")
      (node (ref "U10") (pin "93") (pinfunction "PB7_93") (pintype "bidirectional"))
      (node (ref "U11") (pin "1") (pinfunction "TXD_1") (pintype "power_in"))
    )
    (net (code "66") (name "/USART1_TX_B6") (class "Default")
      (node (ref "U10") (pin "92") (pinfunction "PB6_92") (pintype "bidirectional"))
      (node (ref "U11") (pin "5") (pinfunction "RXD_5") (pintype "power_in"))
    )
    (net (code "67") (name "/USART2_RX_D6") (class "Default")
      (node (ref "M12") (pin "22") (pinfunction "Txd_22") (pintype "passive"))
      (node (ref "U10") (pin "87") (pinfunction "PD6_87") (pintype "bidirectional"))
    )
    (net (code "68") (name "/USART2_TX_D5") (class "Default")
      (node (ref "M12") (pin "21") (pinfunction "Rxd_21") (pintype "passive"))
      (node (ref "U10") (pin "86") (pinfunction "PD5_86") (pintype "bidirectional"))
    )
    (net (code "69") (name "/VCC") (class "Default")
      (node (ref "T3") (pin "4") (pinfunction "VDD_4") (pintype "passive"))
    )
    (net (code "70") (name "/Vdda") (class "Default")
      (node (ref "C83") (pin "2") (pinfunction "2_2") (pintype "passive"))
      (node (ref "C84") (pin "2") (pinfunction "2_2") (pintype "passive"))
      (node (ref "R53") (pin "1") (pinfunction "1_1") (pintype "passive"))
      (node (ref "U10") (pin "21") (pinfunction "VREF+_21") (pintype "power_in"))
      (node (ref "U10") (pin "22") (pinfunction "VDDA_22") (pintype "power_in"))
    )
    (net (code "71") (name "GND") (class "Default")
      (node (ref "C100") (pin "1") (pinfunction "1_1") (pintype "passive"))
      (node (ref "C101") (pin "1") (pinfunction "1_1") (pintype "passive"))
      (node (ref "C102") (pin "1") (pinfunction "1_1") (pintype "passive"))
      (node (ref "C103") (pin "1") (pinfunction "1_1") (pintype "passive"))
      (node (ref "C104") (pin "1") (pinfunction "1_1") (pintype "passive"))
      (node (ref "C105") (pin "1") (pinfunction "1_1") (pintype "passive"))
      (node (ref "C106") (pin "2") (pinfunction "2_2") (pintype "passive"))
      (node (ref "C107") (pin "2") (pinfunction "2_2") (pintype "passive"))
      (node (ref "C108") (pin "2") (pinfunction "2_2") (pintype "passive"))
      (node (ref "C83") (pin "1") (pinfunction "1_1") (pintype "passive"))
      (node (ref "C84") (pin "1") (pinfunction "1_1") (pintype "passive"))
      (node (ref "C85") (pin "2") (pinfunction "2_2") (pintype "passive"))
      (node (ref "C86") (pin "1") (pinfunction "1_1") (pintype "passive"))
      (node (ref "C87") (pin "1") (pinfunction "1_1") (pintype "passive"))
      (node (ref "C88") (pin "1") (pinfunction "1_1") (pintype "passive"))
      (node (ref "C89") (pin "1") (pinfunction "1_1") (pintype "passive"))
      (node (ref "C90") (pin "1") (pinfunction "1_1") (pintype "passive"))
      (node (ref "C91") (pin "1") (pinfunction "1_1") (pintype "passive"))
      (node (ref "C92") (pin "1") (pinfunction "1_1") (pintype "passive"))
      (node (ref "C93") (pin "1") (pinfunction "1_1") (pintype "passive"))
      (node (ref "C94") (pin "1") (pinfunction "1_1") (pintype "passive"))
      (node (ref "C95") (pin "1") (pinfunction "1_1") (pintype "passive"))
      (node (ref "C96") (pin "1") (pinfunction "1_1") (pintype "passive"))
      (node (ref "C97") (pin "1") (pinfunction "1_1") (pintype "passive"))
      (node (ref "C98") (pin "1") (pinfunction "1_1") (pintype "passive"))
      (node (ref "C99") (pin "1") (pinfunction "1_1") (pintype "passive"))
      (node (ref "D16") (pin "K") (pinfunction "K_K") (pintype "passive"))
      (node (ref "D17") (pin "1") (pinfunction "A_1") (pintype "passive"))
      (node (ref "D18") (pin "K") (pinfunction "K_K") (pintype "passive"))
      (node (ref "IO10") (pin "1") (pinfunction "1_1") (pintype "passive"))
      (node (ref "IO11") (pin "1") (pinfunction "1_1") (pintype "passive"))
      (node (ref "IO12") (pin "1") (pinfunction "1_1") (pintype "passive"))
      (node (ref "IO13") (pin "1") (pinfunction "1_1") (pintype "passive"))
      (node (ref "IO14") (pin "1") (pinfunction "1_1") (pintype "passive"))
      (node (ref "IO15") (pin "1") (pinfunction "1_1") (pintype "passive"))
      (node (ref "IO16") (pin "1") (pinfunction "1_1") (pintype "passive"))
      (node (ref "IO9") (pin "1") (pinfunction "1_1") (pintype "passive"))
      (node (ref "J10") (pin "5") (pinfunction "Gnd_5") (pintype "passive"))
      (node (ref "J11") (pin "5") (pinfunction "Gnd_5") (pintype "passive"))
      (node (ref "K10") (pin "1") (pinfunction "1_1") (pintype "passive"))
      (node (ref "K9") (pin "1") (pinfunction "1_1") (pintype "passive"))
      (node (ref "M12") (pin "15") (pinfunction "Gnd_15") (pintype "passive"))
      (node (ref "M13") (pin "15") (pinfunction "GND_MOT_15") (pintype "passive"))
      (node (ref "M13") (pin "9") (pinfunction "GND_9") (pintype "passive"))
      (node (ref "M14") (pin "15") (pinfunction "GND_MOT_15") (pintype "passive"))
      (node (ref "M14") (pin "9") (pinfunction "GND_9") (pintype "passive"))
      (node (ref "M15") (pin "15") (pinfunction "GND_MOT_15") (pintype "passive"))
      (node (ref "M15") (pin "9") (pinfunction "GND_9") (pintype "passive"))
      (node (ref "M16") (pin "15") (pinfunction "GND_MOT_15") (pintype "passive"))
      (node (ref "M16") (pin "9") (pinfunction "GND_9") (pintype "passive"))
      (node (ref "M17") (pin "15") (pinfunction "GND_MOT_15") (pintype "passive"))
      (node (ref "M17") (pin "9") (pinfunction "GND_9") (pintype "passive"))
      (node (ref "P7") (pin "2") (pinfunction "G_2") (pintype "passive"))
      (node (ref "PW3") (pin "2") (pinfunction "2_2") (pintype "passive"))
      (node (ref "Q10") (pin "3") (pinfunction "S_3") (pintype "passive"))
      (node (ref "Q11") (pin "3") (pinfunction "S_3") (pintype "passive"))
      (node (ref "Q12") (pin "3") (pinfunction "S_3") (pintype "passive"))
      (node (ref "Q9") (pin "3") (pinfunction "S_3") (pintype "passive"))
      (node (ref "R58") (pin "1") (pinfunction "1_1") (pintype "passive"))
      (node (ref "R61") (pin "1") (pinfunction "1_1") (pintype "passive"))
      (node (ref "RT17") (pin "1") (pinfunction "1_1") (pintype "passive"))
      (node (ref "RT18") (pin "1") (pinfunction "1_1") (pintype "passive"))
      (node (ref "RT19") (pin "1") (pinfunction "1_1") (pintype "passive"))
      (node (ref "RT20") (pin "1") (pinfunction "1_1") (pintype "passive"))
      (node (ref "RT4") (pin "1") (pinfunction "1_1") (pintype "passive"))
      (node (ref "RT5") (pin "1") (pinfunction "1_1") (pintype "passive"))
      (node (ref "RT6") (pin "1") (pinfunction "1_1") (pintype "passive"))
      (node (ref "T3") (pin "6") (pinfunction "VSS_6") (pintype "passive"))
      (node (ref "U10") (pin "10") (pinfunction "VSS_10") (pintype "power_in"))
      (node (ref "U10") (pin "20") (pinfunction "VSSA_20") (pintype "power_in"))
      (node (ref "U10") (pin "27") (pinfunction "VSS_27") (pintype "power_in"))
      (node (ref "U10") (pin "74") (pinfunction "VSS_74") (pintype "power_in"))
      (node (ref "U10") (pin "99") (pinfunction "VSS_99") (pintype "power_in"))
      (node (ref "U11") (pin "18") (pinfunction "GND_18") (pintype "power_in"))
      (node (ref "U11") (pin "25") (pinfunction "GND_25") (pintype "power_in"))
      (node (ref "U11") (pin "26") (pinfunction "TEST_26") (pintype "power_in"))
      (node (ref "U11") (pin "7") (pinfunction "GND_7") (pintype "power_in"))
      (node (ref "U12") (pin "3") (pinfunction "GND_3") (pintype "power_in"))
      (node (ref "U12") (pin "5") (pinfunction "ON_OFF_N_5") (pintype "input"))
      (node (ref "U12") (pin "6") (pinfunction "TAB_6") (pintype "power_in"))
      (node (ref "U13") (pin "4") (pinfunction "GND_4") (pintype "power_in"))
      (node (ref "U13") (pin "5") (pinfunction "IN-_5") (pintype "input"))
      (node (ref "U14") (pin "4") (pinfunction "GND_4") (pintype "power_in"))
      (node (ref "U14") (pin "5") (pinfunction "IN-_5") (pintype "input"))
      (node (ref "U16") (pin "4") (pinfunction "GND_4") (pintype "power_in"))
      (node (ref "U16") (pin "5") (pinfunction "IN-_5") (pintype "input"))
      (node (ref "VR5") (pin "1") (pinfunction "GND_1") (pintype "passive"))
    )
    (net (code "72") (name "Net-(B2-B)") (class "Default")
      (node (ref "B2") (pin "2") (pinfunction "B_2") (pintype "passive"))
      (node (ref "Q9") (pin "2") (pinfunction "D_2") (pintype "passive"))
    )
    (net (code "73") (name "Net-(D14-PadA)") (class "Default")
      (node (ref "D14") (pin "A") (pinfunction "A_A") (pintype "passive"))
      (node (ref "R59") (pin "1") (pinfunction "1_1") (pintype "passive"))
    )
    (net (code "74") (name "Net-(D15-PadA)") (class "Default")
      (node (ref "D15") (pin "A") (pinfunction "A_A") (pintype "passive"))
      (node (ref "R60") (pin "1") (pinfunction "1_1") (pintype "passive"))
    )
    (net (code "75") (name "Net-(D16-PadA)") (class "Default")
      (node (ref "D16") (pin "A") (pinfunction "A_A") (pintype "passive"))
      (node (ref "R63") (pin "1") (pinfunction "1_1") (pintype "passive"))
    )
    (net (code "76") (name "Net-(D17-K)") (class "Default")
      (node (ref "D17") (pin "2") (pinfunction "K_2") (pintype "passive"))
      (node (ref "L2") (pin "1") (pintype "passive"))
      (node (ref "U12") (pin "2") (pinfunction "OUTPUT_2") (pintype "power_in"))
    )
    (net (code "77") (name "Net-(D18-PadA)") (class "Default")
      (node (ref "D18") (pin "A") (pinfunction "A_A") (pintype "passive"))
      (node (ref "R67") (pin "2") (pinfunction "2_2") (pintype "passive"))
    )
    (net (code "78") (name "Net-(J11-Dm-)") (class "Default")
      (node (ref "J11") (pin "2") (pinfunction "Dm-_2") (pintype "passive"))
      (node (ref "R65") (pin "2") (pinfunction "2_2") (pintype "passive"))
    )
    (net (code "79") (name "Net-(J11-Dp+)") (class "Default")
      (node (ref "J11") (pin "3") (pinfunction "Dp+_3") (pintype "passive"))
      (node (ref "R64") (pin "1") (pinfunction "1_1") (pintype "passive"))
      (node (ref "R66") (pin "2") (pinfunction "2_2") (pintype "passive"))
    )
    (net (code "80") (name "Net-(M13-A1)") (class "Default")
      (node (ref "JP1") (pin "3") (pinfunction "3_3") (pintype "passive"))
      (node (ref "M13") (pin "12") (pinfunction "A1_12") (pintype "passive"))
    )
    (net (code "81") (name "Net-(M13-A2)") (class "Default")
      (node (ref "JP1") (pin "4") (pinfunction "4_4") (pintype "passive"))
      (node (ref "M13") (pin "11") (pinfunction "A2_11") (pintype "passive"))
    )
    (net (code "82") (name "Net-(M13-B1)") (class "Default")
      (node (ref "JP1") (pin "2") (pinfunction "2_2") (pintype "passive"))
      (node (ref "M13") (pin "13") (pinfunction "B1_13") (pintype "passive"))
    )
    (net (code "83") (name "Net-(M13-B2)") (class "Default")
      (node (ref "JP1") (pin "1") (pinfunction "1_1") (pintype "passive"))
      (node (ref "M13") (pin "14") (pinfunction "B2_14") (pintype "passive"))
    )
    (net (code "84") (name "Net-(M14-A1)") (class "Default")
      (node (ref "JP2") (pin "3") (pinfunction "3_3") (pintype "passive"))
      (node (ref "M14") (pin "12") (pinfunction "A1_12") (pintype "passive"))
    )
    (net (code "85") (name "Net-(M14-A2)") (class "Default")
      (node (ref "JP2") (pin "4") (pinfunction "4_4") (pintype "passive"))
      (node (ref "M14") (pin "11") (pinfunction "A2_11") (pintype "passive"))
    )
    (net (code "86") (name "Net-(M14-B1)") (class "Default")
      (node (ref "JP2") (pin "2") (pinfunction "2_2") (pintype "passive"))
      (node (ref "M14") (pin "13") (pinfunction "B1_13") (pintype "passive"))
    )
    (net (code "87") (name "Net-(M14-B2)") (class "Default")
      (node (ref "JP2") (pin "1") (pinfunction "1_1") (pintype "passive"))
      (node (ref "M14") (pin "14") (pinfunction "B2_14") (pintype "passive"))
    )
    (net (code "88") (name "Net-(M15-A1)") (class "Default")
      (node (ref "JP3") (pin "3") (pinfunction "3_3") (pintype "passive"))
      (node (ref "M15") (pin "12") (pinfunction "A1_12") (pintype "passive"))
    )
    (net (code "89") (name "Net-(M15-A2)") (class "Default")
      (node (ref "JP3") (pin "4") (pinfunction "4_4") (pintype "passive"))
      (node (ref "M15") (pin "11") (pinfunction "A2_11") (pintype "passive"))
    )
    (net (code "90") (name "Net-(M15-B1)") (class "Default")
      (node (ref "JP3") (pin "2") (pinfunction "2_2") (pintype "passive"))
      (node (ref "M15") (pin "13") (pinfunction "B1_13") (pintype "passive"))
    )
    (net (code "91") (name "Net-(M15-B2)") (class "Default")
      (node (ref "JP3") (pin "1") (pinfunction "1_1") (pintype "passive"))
      (node (ref "M15") (pin "14") (pinfunction "B2_14") (pintype "passive"))
    )
    (net (code "92") (name "Net-(M16-A1)") (class "Default")
      (node (ref "JP4") (pin "3") (pinfunction "3_3") (pintype "passive"))
      (node (ref "M16") (pin "12") (pinfunction "A1_12") (pintype "passive"))
    )
    (net (code "93") (name "Net-(M16-A2)") (class "Default")
      (node (ref "JP4") (pin "4") (pinfunction "4_4") (pintype "passive"))
      (node (ref "M16") (pin "11") (pinfunction "A2_11") (pintype "passive"))
    )
    (net (code "94") (name "Net-(M16-B1)") (class "Default")
      (node (ref "JP4") (pin "2") (pinfunction "2_2") (pintype "passive"))
      (node (ref "M16") (pin "13") (pinfunction "B1_13") (pintype "passive"))
    )
    (net (code "95") (name "Net-(M16-B2)") (class "Default")
      (node (ref "JP4") (pin "1") (pinfunction "1_1") (pintype "passive"))
      (node (ref "M16") (pin "14") (pinfunction "B2_14") (pintype "passive"))
    )
    (net (code "96") (name "Net-(M17-A1)") (class "Default")
      (node (ref "JP5") (pin "3") (pinfunction "3_3") (pintype "passive"))
      (node (ref "M17") (pin "12") (pinfunction "A1_12") (pintype "passive"))
    )
    (net (code "97") (name "Net-(M17-A2)") (class "Default")
      (node (ref "JP5") (pin "4") (pinfunction "4_4") (pintype "passive"))
      (node (ref "M17") (pin "11") (pinfunction "A2_11") (pintype "passive"))
    )
    (net (code "98") (name "Net-(M17-B1)") (class "Default")
      (node (ref "JP5") (pin "2") (pinfunction "2_2") (pintype "passive"))
      (node (ref "M17") (pin "13") (pinfunction "B1_13") (pintype "passive"))
    )
    (net (code "99") (name "Net-(M17-B2)") (class "Default")
      (node (ref "JP5") (pin "1") (pinfunction "1_1") (pintype "passive"))
      (node (ref "M17") (pin "14") (pinfunction "B2_14") (pintype "passive"))
    )
    (net (code "100") (name "Net-(Q10-D)") (class "Default")
      (node (ref "PW4") (pin "2") (pinfunction "2_2") (pintype "passive"))
      (node (ref "Q10") (pin "2") (pinfunction "D_2") (pintype "passive"))
    )
    (net (code "101") (name "Net-(Q10-G)") (class "Default")
      (node (ref "Q10") (pin "1") (pinfunction "G_1") (pintype "passive"))
      (node (ref "R68") (pin "2") (pinfunction "2_2") (pintype "passive"))
      (node (ref "R69") (pin "2") (pinfunction "2_2") (pintype "passive"))
    )
    (net (code "102") (name "Net-(Q11-D)") (class "Default")
      (node (ref "PW5") (pin "2") (pinfunction "2_2") (pintype "passive"))
      (node (ref "Q11") (pin "2") (pinfunction "D_2") (pintype "passive"))
    )
    (net (code "103") (name "Net-(Q11-G)") (class "Default")
      (node (ref "Q11") (pin "1") (pinfunction "G_1") (pintype "passive"))
      (node (ref "R70") (pin "2") (pinfunction "2_2") (pintype "passive"))
      (node (ref "R71") (pin "2") (pinfunction "2_2") (pintype "passive"))
    )
    (net (code "104") (name "Net-(Q12-D)") (class "Default")
      (node (ref "PW6") (pin "2") (pinfunction "2_2") (pintype "passive"))
      (node (ref "Q12") (pin "2") (pinfunction "D_2") (pintype "passive"))
    )
    (net (code "105") (name "Net-(Q12-G)") (class "Default")
      (node (ref "Q12") (pin "1") (pinfunction "G_1") (pintype "passive"))
      (node (ref "R72") (pin "2") (pinfunction "2_2") (pintype "passive"))
      (node (ref "R73") (pin "2") (pinfunction "2_2") (pintype "passive"))
    )
    (net (code "106") (name "Net-(U10B-BOOT0)") (class "Default")
      (node (ref "R58") (pin "2") (pinfunction "2_2") (pintype "passive"))
      (node (ref "U10") (pin "94") (pinfunction "BOOT0_94") (pintype "input"))
    )
    (net (code "107") (name "Net-(U10B-PH0{slash}OSC_IN)") (class "Default")
      (node (ref "C96") (pin "2") (pinfunction "2_2") (pintype "passive"))
      (node (ref "U10") (pin "12") (pinfunction "PH0/OSC_IN_12") (pintype "bidirectional"))
      (node (ref "Y5") (pin "3") (pinfunction "OSC2_3") (pintype "passive"))
    )
    (net (code "108") (name "Net-(U10B-PH1{slash}OSC_OUT)") (class "Default")
      (node (ref "C95") (pin "2") (pinfunction "2_2") (pintype "passive"))
      (node (ref "U10") (pin "13") (pinfunction "PH1/OSC_OUT_13") (pintype "bidirectional"))
      (node (ref "Y5") (pin "1") (pinfunction "OSC1_1") (pintype "passive"))
    )
    (net (code "109") (name "Net-(U10C-VCAP_1)") (class "Default")
      (node (ref "C87") (pin "2") (pinfunction "2_2") (pintype "passive"))
      (node (ref "U10") (pin "49") (pinfunction "VCAP_1_49") (pintype "power_in"))
    )
    (net (code "110") (name "Net-(U10C-VCAP_2)") (class "Default")
      (node (ref "C86") (pin "2") (pinfunction "2_2") (pintype "passive"))
      (node (ref "U10") (pin "73") (pinfunction "VCAP_2_73") (pintype "power_in"))
    )
    (net (code "111") (name "Net-(U11-DCD_N)") (class "Default")
      (node (ref "R62") (pin "1") (pinfunction "1_1") (pintype "passive"))
      (node (ref "U11") (pin "10") (pinfunction "DCD_N_10") (pintype "power_in"))
    )
    (net (code "112") (name "Net-(U13-OUTH)") (class "Default")
      (node (ref "R68") (pin "1") (pinfunction "1_1") (pintype "passive"))
      (node (ref "U13") (pin "2") (pinfunction "OUTH_2") (pintype "power_in"))
    )
    (net (code "113") (name "Net-(U13-OUTL)") (class "Default")
      (node (ref "R69") (pin "1") (pinfunction "1_1") (pintype "passive"))
      (node (ref "U13") (pin "3") (pinfunction "OUTL_3") (pintype "power_in"))
    )
    (net (code "114") (name "Net-(U14-OUTH)") (class "Default")
      (node (ref "R70") (pin "1") (pinfunction "1_1") (pintype "passive"))
      (node (ref "U14") (pin "2") (pinfunction "OUTH_2") (pintype "power_in"))
    )
    (net (code "115") (name "Net-(U14-OUTL)") (class "Default")
      (node (ref "R71") (pin "1") (pinfunction "1_1") (pintype "passive"))
      (node (ref "U14") (pin "3") (pinfunction "OUTL_3") (pintype "power_in"))
    )
    (net (code "116") (name "Net-(U16-OUTH)") (class "Default")
      (node (ref "R72") (pin "1") (pinfunction "1_1") (pintype "passive"))
      (node (ref "U16") (pin "2") (pinfunction "OUTH_2") (pintype "power_in"))
    )
    (net (code "117") (name "Net-(U16-OUTL)") (class "Default")
      (node (ref "R73") (pin "1") (pinfunction "1_1") (pintype "passive"))
      (node (ref "U16") (pin "3") (pinfunction "OUTL_3") (pintype "power_in"))
    )
    (net (code "118") (name "V3") (class "Default")
      (node (ref "B2") (pin "1") (pinfunction "A_1") (pintype "passive"))
      (node (ref "C105") (pin "2") (pinfunction "2_2") (pintype "passive"))
      (node (ref "C85") (pin "1") (pinfunction "1_1") (pintype "passive"))
      (node (ref "C88") (pin "2") (pinfunction "2_2") (pintype "passive"))
      (node (ref "C89") (pin "2") (pinfunction "2_2") (pintype "passive"))
      (node (ref "C90") (pin "2") (pinfunction "2_2") (pintype "passive"))
      (node (ref "C91") (pin "2") (pinfunction "2_2") (pintype "passive"))
      (node (ref "C92") (pin "2") (pinfunction "2_2") (pintype "passive"))
      (node (ref "C93") (pin "2") (pinfunction "2_2") (pintype "passive"))
      (node (ref "C94") (pin "2") (pinfunction "2_2") (pintype "passive"))
      (node (ref "C97") (pin "2") (pinfunction "2_2") (pintype "passive"))
      (node (ref "IO10") (pin "3") (pinfunction "3_3") (pintype "passive"))
      (node (ref "IO11") (pin "3") (pinfunction "3_3") (pintype "passive"))
      (node (ref "IO12") (pin "3") (pinfunction "3_3") (pintype "passive"))
      (node (ref "IO13") (pin "3") (pinfunction "3_3") (pintype "passive"))
      (node (ref "IO14") (pin "3") (pinfunction "3_3") (pintype "passive"))
      (node (ref "IO15") (pin "3") (pinfunction "3_3") (pintype "passive"))
      (node (ref "IO16") (pin "3") (pinfunction "3_3") (pintype "passive"))
      (node (ref "IO9") (pin "3") (pinfunction "3_3") (pintype "passive"))
      (node (ref "M12") (pin "8") (pinfunction "Vcc_8") (pintype "passive"))
      (node (ref "R51") (pin "1") (pinfunction "1_1") (pintype "passive"))
      (node (ref "R52") (pin "1") (pinfunction "1_1") (pintype "passive"))
      (node (ref "R53") (pin "2") (pinfunction "2_2") (pintype "passive"))
      (node (ref "R54") (pin "1") (pinfunction "1_1") (pintype "passive"))
      (node (ref "R55") (pin "1") (pinfunction "1_1") (pintype "passive"))
      (node (ref "R56") (pin "1") (pinfunction "1_1") (pintype "passive"))
      (node (ref "R57") (pin "1") (pinfunction "1_1") (pintype "passive"))
      (node (ref "R59") (pin "2") (pinfunction "2_2") (pintype "passive"))
      (node (ref "R60") (pin "2") (pinfunction "2_2") (pintype "passive"))
      (node (ref "R63") (pin "2") (pinfunction "2_2") (pintype "passive"))
      (node (ref "RP4") (pin "2") (pinfunction "TAP_2") (pintype "passive"))
      (node (ref "RP4") (pin "3") (pinfunction "TOP_3") (pintype "passive"))
      (node (ref "RP5") (pin "2") (pinfunction "TAP_2") (pintype "passive"))
      (node (ref "RP5") (pin "3") (pinfunction "TOP_3") (pintype "passive"))
      (node (ref "RP6") (pin "2") (pinfunction "TAP_2") (pintype "passive"))
      (node (ref "RP6") (pin "3") (pinfunction "TOP_3") (pintype "passive"))
      (node (ref "U10") (pin "100") (pinfunction "VDD_100") (pintype "power_in"))
      (node (ref "U10") (pin "11") (pinfunction "VDD_11") (pintype "power_in"))
      (node (ref "U10") (pin "19") (pinfunction "VDD_19") (pintype "power_in"))
      (node (ref "U10") (pin "28") (pinfunction "VDD_28") (pintype "power_in"))
      (node (ref "U10") (pin "50") (pinfunction "VDD_50") (pintype "power_in"))
      (node (ref "U10") (pin "6") (pinfunction "VBAT_6") (pintype "power_in"))
      (node (ref "U10") (pin "75") (pinfunction "VDD_75") (pintype "power_in"))
      (node (ref "VR5") (pin "2") (pinfunction "Vout_2") (pintype "passive"))
    )
    (net (code "119") (name "V5") (class "Default")
      (node (ref "C101") (pin "2") (pinfunction "2_2") (pintype "passive"))
      (node (ref "C103") (pin "2") (pinfunction "2_2") (pintype "passive"))
      (node (ref "C104") (pin "2") (pinfunction "2_2") (pintype "passive"))
      (node (ref "C106") (pin "1") (pinfunction "1_1") (pintype "passive"))
      (node (ref "C108") (pin "1") (pinfunction "1_1") (pintype "passive"))
      (node (ref "J11") (pin "1") (pinfunction "Vbus_1") (pintype "passive"))
      (node (ref "L2") (pin "2") (pintype "passive"))
      (node (ref "R67") (pin "1") (pinfunction "1_1") (pintype "passive"))
      (node (ref "RT19") (pin "2") (pinfunction "2_2") (pintype "passive"))
      (node (ref "RT20") (pin "2") (pinfunction "2_2") (pintype "passive"))
      (node (ref "U11") (pin "20") (pinfunction "VDD_5_20") (pintype "power_in"))
      (node (ref "U12") (pin "4") (pinfunction "FEEDBACK_4") (pintype "input"))
      (node (ref "VR5") (pin "3") (pinfunction "Vin_3") (pintype "passive"))
    )
    (net (code "120") (name "V12") (class "Default")
      (node (ref "C107") (pin "1") (pinfunction "1_1") (pintype "passive"))
      (node (ref "M13") (pin "16") (pinfunction "VCC_MOT_16") (pintype "passive"))
      (node (ref "M14") (pin "16") (pinfunction "VCC_MOT_16") (pintype "passive"))
      (node (ref "M15") (pin "16") (pinfunction "VCC_MOT_16") (pintype "passive"))
      (node (ref "M16") (pin "16") (pinfunction "VCC_MOT_16") (pintype "passive"))
      (node (ref "M17") (pin "16") (pinfunction "VCC_MOT_16") (pintype "passive"))
      (node (ref "P7") (pin "1") (pinfunction "V_1") (pintype "passive"))
      (node (ref "PW3") (pin "1") (pinfunction "1_1") (pintype "passive"))
      (node (ref "PW4") (pin "1") (pinfunction "1_1") (pintype "passive"))
      (node (ref "PW5") (pin "1") (pinfunction "1_1") (pintype "passive"))
      (node (ref "PW6") (pin "1") (pinfunction "1_1") (pintype "passive"))
      (node (ref "RT17") (pin "2") (pinfunction "2_2") (pintype "passive"))
      (node (ref "RT18") (pin "2") (pinfunction "2_2") (pintype "passive"))
      (node (ref "U12") (pin "1") (pinfunction "VIN_1") (pintype "power_in"))
      (node (ref "U13") (pin "1") (pinfunction "VDD_1") (pintype "power_in"))
      (node (ref "U14") (pin "1") (pinfunction "VDD_1") (pintype "power_in"))
      (node (ref "U16") (pin "1") (pinfunction "VDD_1") (pintype "power_in"))
    )
    (net (code "121") (name "unconnected-(J10-Id-Pad4)") (class "Default")
      (node (ref "J10") (pin "4") (pinfunction "Id_4") (pintype "passive"))
    )
    (net (code "122") (name "unconnected-(J10-Vbus-Pad1)") (class "Default")
      (node (ref "J10") (pin "1") (pinfunction "Vbus_1") (pintype "passive"))
    )
    (net (code "123") (name "unconnected-(J11-Id-Pad4)") (class "Default")
      (node (ref "J11") (pin "4") (pinfunction "Id_4") (pintype "passive"))
    )
    (net (code "124") (name "unconnected-(M12-Adc-Pad2)") (class "Default")
      (node (ref "M12") (pin "2") (pinfunction "Adc_2") (pintype "passive"))
    )
    (net (code "125") (name "unconnected-(M12-Cs-Pad14)") (class "Default")
      (node (ref "M12") (pin "14") (pinfunction "Cs_14") (pintype "passive"))
    )
    (net (code "126") (name "unconnected-(M12-En-Pad3)") (class "Default")
      (node (ref "M12") (pin "3") (pinfunction "En_3") (pintype "passive"))
    )
    (net (code "127") (name "unconnected-(M12-Io0-Pad18)") (class "Default")
      (node (ref "M12") (pin "18") (pinfunction "Io0_18") (pintype "passive"))
    )
    (net (code "128") (name "unconnected-(M12-Io2-Pad17)") (class "Default")
      (node (ref "M12") (pin "17") (pinfunction "Io2_17") (pintype "passive"))
    )
    (net (code "129") (name "unconnected-(M12-Io4-Pad19)") (class "Default")
      (node (ref "M12") (pin "19") (pinfunction "Io4_19") (pintype "passive"))
    )
    (net (code "130") (name "unconnected-(M12-Io5-Pad20)") (class "Default")
      (node (ref "M12") (pin "20") (pinfunction "Io5_20") (pintype "passive"))
    )
    (net (code "131") (name "unconnected-(M12-Io9-Pad12)") (class "Default")
      (node (ref "M12") (pin "12") (pinfunction "Io9_12") (pintype "passive"))
    )
    (net (code "132") (name "unconnected-(M12-Io10-Pad11)") (class "Default")
      (node (ref "M12") (pin "11") (pinfunction "Io10_11") (pintype "passive"))
    )
    (net (code "133") (name "unconnected-(M12-Io12-Pad6)") (class "Default")
      (node (ref "M12") (pin "6") (pinfunction "Io12_6") (pintype "passive"))
    )
    (net (code "134") (name "unconnected-(M12-Io13-Pad7)") (class "Default")
      (node (ref "M12") (pin "7") (pinfunction "Io13_7") (pintype "passive"))
    )
    (net (code "135") (name "unconnected-(M12-Io14-Pad5)") (class "Default")
      (node (ref "M12") (pin "5") (pinfunction "Io14_5") (pintype "passive"))
    )
    (net (code "136") (name "unconnected-(M12-Io15-Pad16)") (class "Default")
      (node (ref "M12") (pin "16") (pinfunction "Io15_16") (pintype "passive"))
    )
    (net (code "137") (name "unconnected-(M12-Io16-Pad4)") (class "Default")
      (node (ref "M12") (pin "4") (pinfunction "Io16_4") (pintype "passive"))
    )
    (net (code "138") (name "unconnected-(M12-Miso-Pad13)") (class "Default")
      (node (ref "M12") (pin "13") (pinfunction "Miso_13") (pintype "passive"))
    )
    (net (code "139") (name "unconnected-(M12-Mosi-Pad10)") (class "Default")
      (node (ref "M12") (pin "10") (pinfunction "Mosi_10") (pintype "passive"))
    )
    (net (code "140") (name "unconnected-(M12-Sclk-Pad9)") (class "Default")
      (node (ref "M12") (pin "9") (pinfunction "Sclk_9") (pintype "passive"))
    )
    (net (code "141") (name "unconnected-(M13-ENABLE-Pad1)") (class "Default")
      (node (ref "M13") (pin "1") (pinfunction "ENABLE_1") (pintype "passive"))
    )
    (net (code "142") (name "unconnected-(M13-FAULT-Pad10)") (class "Default")
      (node (ref "M13") (pin "10") (pinfunction "FAULT_10") (pintype "passive"))
    )
    (net (code "143") (name "unconnected-(M13-M0-Pad2)") (class "Default")
      (node (ref "M13") (pin "2") (pinfunction "M0_2") (pintype "passive"))
    )
    (net (code "144") (name "unconnected-(M13-M1-Pad3)") (class "Default")
      (node (ref "M13") (pin "3") (pinfunction "M1_3") (pintype "passive"))
    )
    (net (code "145") (name "unconnected-(M13-M2-Pad4)") (class "Default")
      (node (ref "M13") (pin "4") (pinfunction "M2_4") (pintype "passive"))
    )
    (net (code "146") (name "unconnected-(M14-ENABLE-Pad1)") (class "Default")
      (node (ref "M14") (pin "1") (pinfunction "ENABLE_1") (pintype "passive"))
    )
    (net (code "147") (name "unconnected-(M14-FAULT-Pad10)") (class "Default")
      (node (ref "M14") (pin "10") (pinfunction "FAULT_10") (pintype "passive"))
    )
    (net (code "148") (name "unconnected-(M14-M0-Pad2)") (class "Default")
      (node (ref "M14") (pin "2") (pinfunction "M0_2") (pintype "passive"))
    )
    (net (code "149") (name "unconnected-(M14-M1-Pad3)") (class "Default")
      (node (ref "M14") (pin "3") (pinfunction "M1_3") (pintype "passive"))
    )
    (net (code "150") (name "unconnected-(M14-M2-Pad4)") (class "Default")
      (node (ref "M14") (pin "4") (pinfunction "M2_4") (pintype "passive"))
    )
    (net (code "151") (name "unconnected-(M15-ENABLE-Pad1)") (class "Default")
      (node (ref "M15") (pin "1") (pinfunction "ENABLE_1") (pintype "passive"))
    )
    (net (code "152") (name "unconnected-(M15-FAULT-Pad10)") (class "Default")
      (node (ref "M15") (pin "10") (pinfunction "FAULT_10") (pintype "passive"))
    )
    (net (code "153") (name "unconnected-(M15-M0-Pad2)") (class "Default")
      (node (ref "M15") (pin "2") (pinfunction "M0_2") (pintype "passive"))
    )
    (net (code "154") (name "unconnected-(M15-M1-Pad3)") (class "Default")
      (node (ref "M15") (pin "3") (pinfunction "M1_3") (pintype "passive"))
    )
    (net (code "155") (name "unconnected-(M15-M2-Pad4)") (class "Default")
      (node (ref "M15") (pin "4") (pinfunction "M2_4") (pintype "passive"))
    )
    (net (code "156") (name "unconnected-(M16-ENABLE-Pad1)") (class "Default")
      (node (ref "M16") (pin "1") (pinfunction "ENABLE_1") (pintype "passive"))
    )
    (net (code "157") (name "unconnected-(M16-FAULT-Pad10)") (class "Default")
      (node (ref "M16") (pin "10") (pinfunction "FAULT_10") (pintype "passive"))
    )
    (net (code "158") (name "unconnected-(M16-M0-Pad2)") (class "Default")
      (node (ref "M16") (pin "2") (pinfunction "M0_2") (pintype "passive"))
    )
    (net (code "159") (name "unconnected-(M16-M1-Pad3)") (class "Default")
      (node (ref "M16") (pin "3") (pinfunction "M1_3") (pintype "passive"))
    )
    (net (code "160") (name "unconnected-(M16-M2-Pad4)") (class "Default")
      (node (ref "M16") (pin "4") (pinfunction "M2_4") (pintype "passive"))
    )
    (net (code "161") (name "unconnected-(M17-ENABLE-Pad1)") (class "Default")
      (node (ref "M17") (pin "1") (pinfunction "ENABLE_1") (pintype "passive"))
    )
    (net (code "162") (name "unconnected-(M17-FAULT-Pad10)") (class "Default")
      (node (ref "M17") (pin "10") (pinfunction "FAULT_10") (pintype "passive"))
    )
    (net (code "163") (name "unconnected-(M17-M0-Pad2)") (class "Default")
      (node (ref "M17") (pin "2") (pinfunction "M0_2") (pintype "passive"))
    )
    (net (code "164") (name "unconnected-(M17-M1-Pad3)") (class "Default")
      (node (ref "M17") (pin "3") (pinfunction "M1_3") (pintype "passive"))
    )
    (net (code "165") (name "unconnected-(M17-M2-Pad4)") (class "Default")
      (node (ref "M17") (pin "4") (pinfunction "M2_4") (pintype "passive"))
    )
    (net (code "166") (name "unconnected-(T3-CD-Pad9)") (class "Default")
      (node (ref "T3") (pin "9") (pinfunction "CD_9") (pintype "passive"))
    )
    (net (code "167") (name "unconnected-(U10A-PA0{slash}WKUP-Pad23)") (class "Default")
      (node (ref "U10") (pin "23") (pinfunction "PA0/WKUP_23") (pintype "bidirectional"))
    )
    (net (code "168") (name "unconnected-(U10A-PA1-Pad24)") (class "Default")
      (node (ref "U10") (pin "24") (pinfunction "PA1_24") (pintype "bidirectional"))
    )
    (net (code "169") (name "unconnected-(U10A-PA2-Pad25)") (class "Default")
      (node (ref "U10") (pin "25") (pinfunction "PA2_25") (pintype "bidirectional"))
    )
    (net (code "170") (name "unconnected-(U10A-PA3-Pad26)") (class "Default")
      (node (ref "U10") (pin "26") (pinfunction "PA3_26") (pintype "bidirectional"))
    )
    (net (code "171") (name "unconnected-(U10A-PA4-Pad29)") (class "Default")
      (node (ref "U10") (pin "29") (pinfunction "PA4_29") (pintype "bidirectional"))
    )
    (net (code "172") (name "unconnected-(U10A-PA5-Pad30)") (class "Default")
      (node (ref "U10") (pin "30") (pinfunction "PA5_30") (pintype "bidirectional"))
    )
    (net (code "173") (name "unconnected-(U10A-PA6-Pad31)") (class "Default")
      (node (ref "U10") (pin "31") (pinfunction "PA6_31") (pintype "bidirectional"))
    )
    (net (code "174") (name "unconnected-(U10A-PA7-Pad32)") (class "Default")
      (node (ref "U10") (pin "32") (pinfunction "PA7_32") (pintype "bidirectional"))
    )
    (net (code "175") (name "unconnected-(U10A-PA8-Pad67)") (class "Default")
      (node (ref "U10") (pin "67") (pinfunction "PA8_67") (pintype "bidirectional"))
    )
    (net (code "176") (name "unconnected-(U10A-PA15-Pad77)") (class "Default")
      (node (ref "U10") (pin "77") (pinfunction "PA15_77") (pintype "bidirectional"))
    )
    (net (code "177") (name "unconnected-(U10A-PC3-Pad18)") (class "Default")
      (node (ref "U10") (pin "18") (pinfunction "PC3_18") (pintype "bidirectional"))
    )
    (net (code "178") (name "unconnected-(U10A-PC4-Pad33)") (class "Default")
      (node (ref "U10") (pin "33") (pinfunction "PC4_33") (pintype "bidirectional"))
    )
    (net (code "179") (name "unconnected-(U10A-PC5-Pad34)") (class "Default")
      (node (ref "U10") (pin "34") (pinfunction "PC5_34") (pintype "bidirectional"))
    )
    (net (code "180") (name "unconnected-(U10A-PC13-Pad7)") (class "Default")
      (node (ref "U10") (pin "7") (pinfunction "PC13_7") (pintype "bidirectional"))
    )
    (net (code "181") (name "unconnected-(U10A-PC14{slash}OSC32_IN-Pad8)") (class "Default")
      (node (ref "U10") (pin "8") (pinfunction "PC14/OSC32_IN_8") (pintype "bidirectional"))
    )
    (net (code "182") (name "unconnected-(U10A-PC15{slash}OSC32_OUT-Pad9)") (class "Default")
      (node (ref "U10") (pin "9") (pinfunction "PC15/OSC32_OUT_9") (pintype "bidirectional"))
    )
    (net (code "183") (name "unconnected-(U11-CTS_N-Pad11)") (class "Default")
      (node (ref "U11") (pin "11") (pinfunction "CTS_N_11") (pintype "power_in"))
    )
    (net (code "184") (name "unconnected-(U11-DSR_N-Pad9)") (class "Default")
      (node (ref "U11") (pin "9") (pinfunction "DSR_N_9") (pintype "power_in"))
    )
    (net (code "185") (name "unconnected-(U11-DTR_N-Pad2)") (class "Default")
      (node (ref "U11") (pin "2") (pinfunction "DTR_N_2") (pintype "power_in"))
    )
    (net (code "186") (name "unconnected-(U11-DTS_N-Pad3)") (class "Default")
      (node (ref "U11") (pin "3") (pinfunction "DTS_N_3") (pintype "power_in"))
    )
    (net (code "187") (name "unconnected-(U11-GP0-Pad22)") (class "Default")
      (node (ref "U11") (pin "22") (pinfunction "GP0_22") (pintype "power_in"))
    )
    (net (code "188") (name "unconnected-(U11-GP1-Pad23)") (class "Default")
      (node (ref "U11") (pin "23") (pinfunction "GP1_23") (pintype "power_in"))
    )
    (net (code "189") (name "unconnected-(U11-GP2-Pad14)") (class "Default")
      (node (ref "U11") (pin "14") (pinfunction "GP2_14") (pintype "power_in"))
    )
    (net (code "190") (name "unconnected-(U11-GP3-Pad13)") (class "Default")
      (node (ref "U11") (pin "13") (pinfunction "GP3_13") (pintype "power_in"))
    )
    (net (code "191") (name "unconnected-(U11-NC-Pad8)") (class "Default")
      (node (ref "U11") (pin "8") (pinfunction "NC_8") (pintype "power_in"))
    )
    (net (code "192") (name "unconnected-(U11-NC-Pad21)") (class "Default")
      (node (ref "U11") (pin "21") (pinfunction "NC_21") (pintype "power_in"))
    )
    (net (code "193") (name "unconnected-(U11-NC-Pad24)") (class "Default")
      (node (ref "U11") (pin "24") (pinfunction "NC_24") (pintype "power_in"))
    )
    (net (code "194") (name "unconnected-(U11-NC-Pad27)") (class "Default")
      (node (ref "U11") (pin "27") (pinfunction "NC_27") (pintype "power_in"))
    )
    (net (code "195") (name "unconnected-(U11-RESERVED-Pad28)") (class "Default")
      (node (ref "U11") (pin "28") (pinfunction "RESERVED_28") (pintype "power_in"))
    )
    (net (code "196") (name "unconnected-(U11-RI_N-Pad6)") (class "Default")
      (node (ref "U11") (pin "6") (pinfunction "RI_N_6") (pintype "power_in"))
    )
    (net (code "197") (name "unconnected-(U11-SHTD_N-Pad12)") (class "Default")
      (node (ref "U11") (pin "12") (pinfunction "SHTD_N_12") (pintype "power_in"))
    )
  )
)
